# DolphinController.net
KiCad netlist of a schematic drawn in Altium Designer
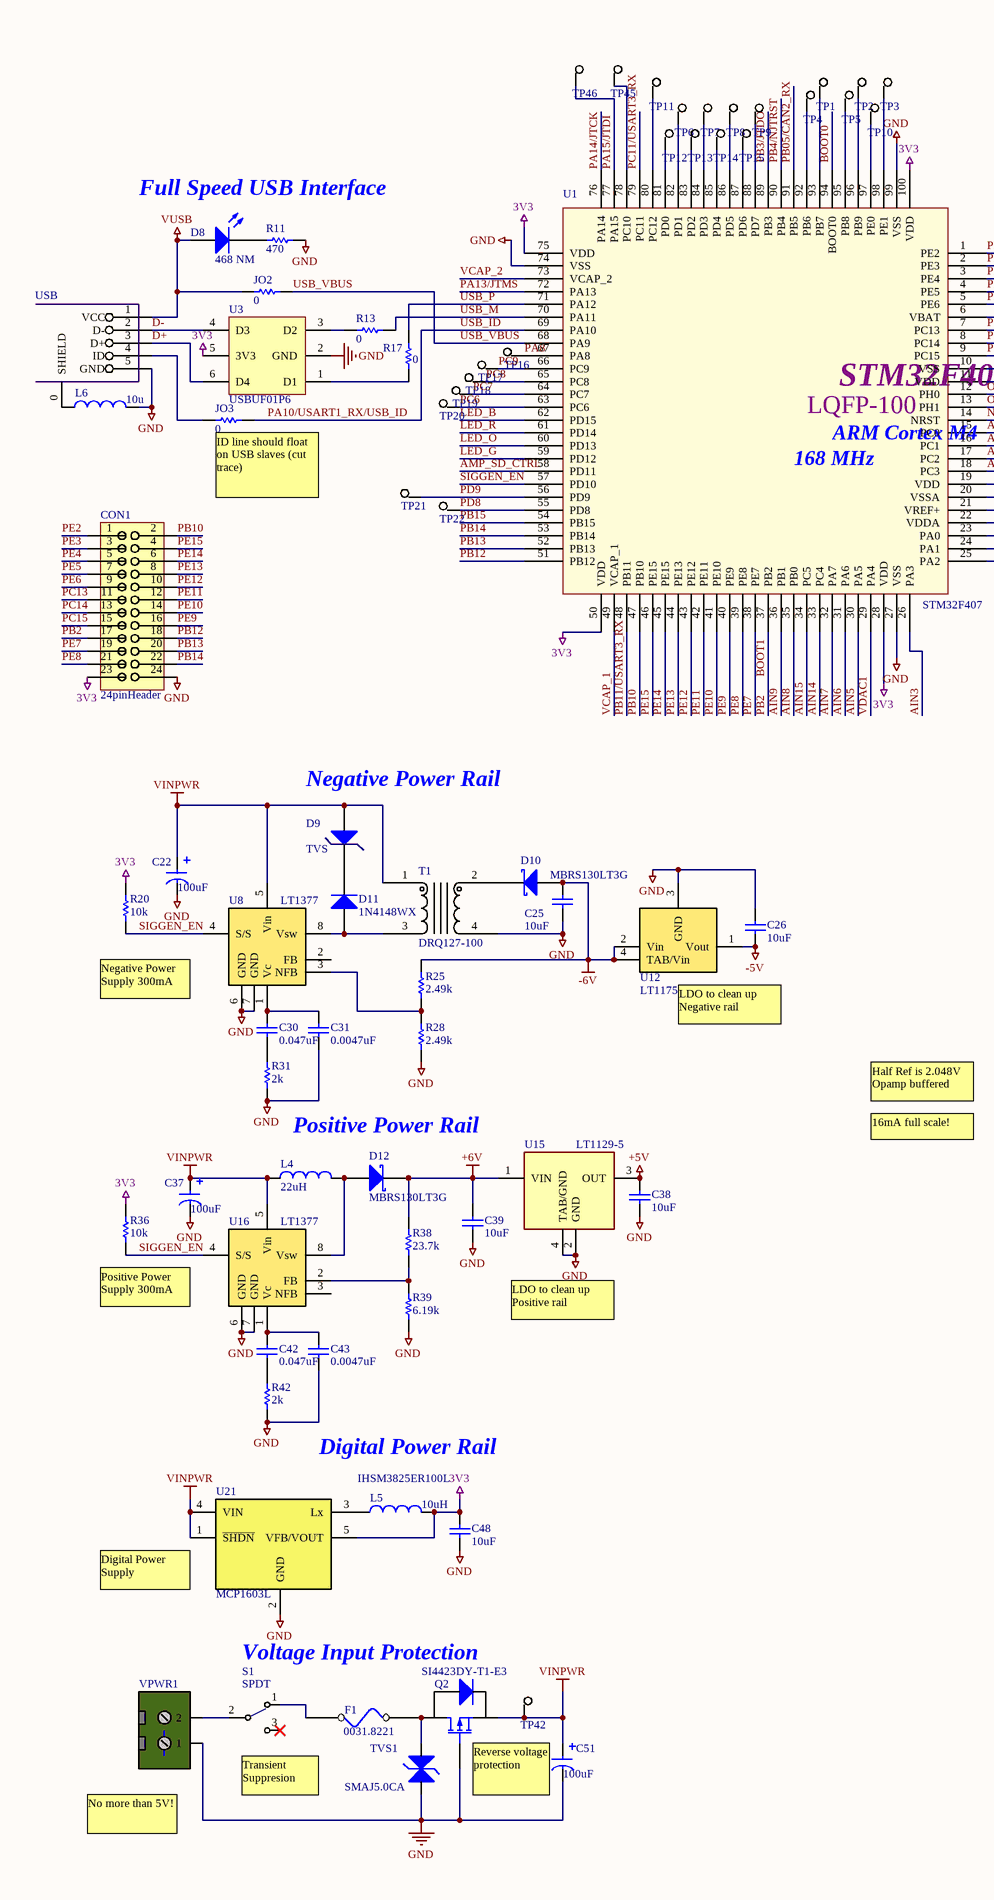
[diagram p0: DolphinController.SchDoc, left]
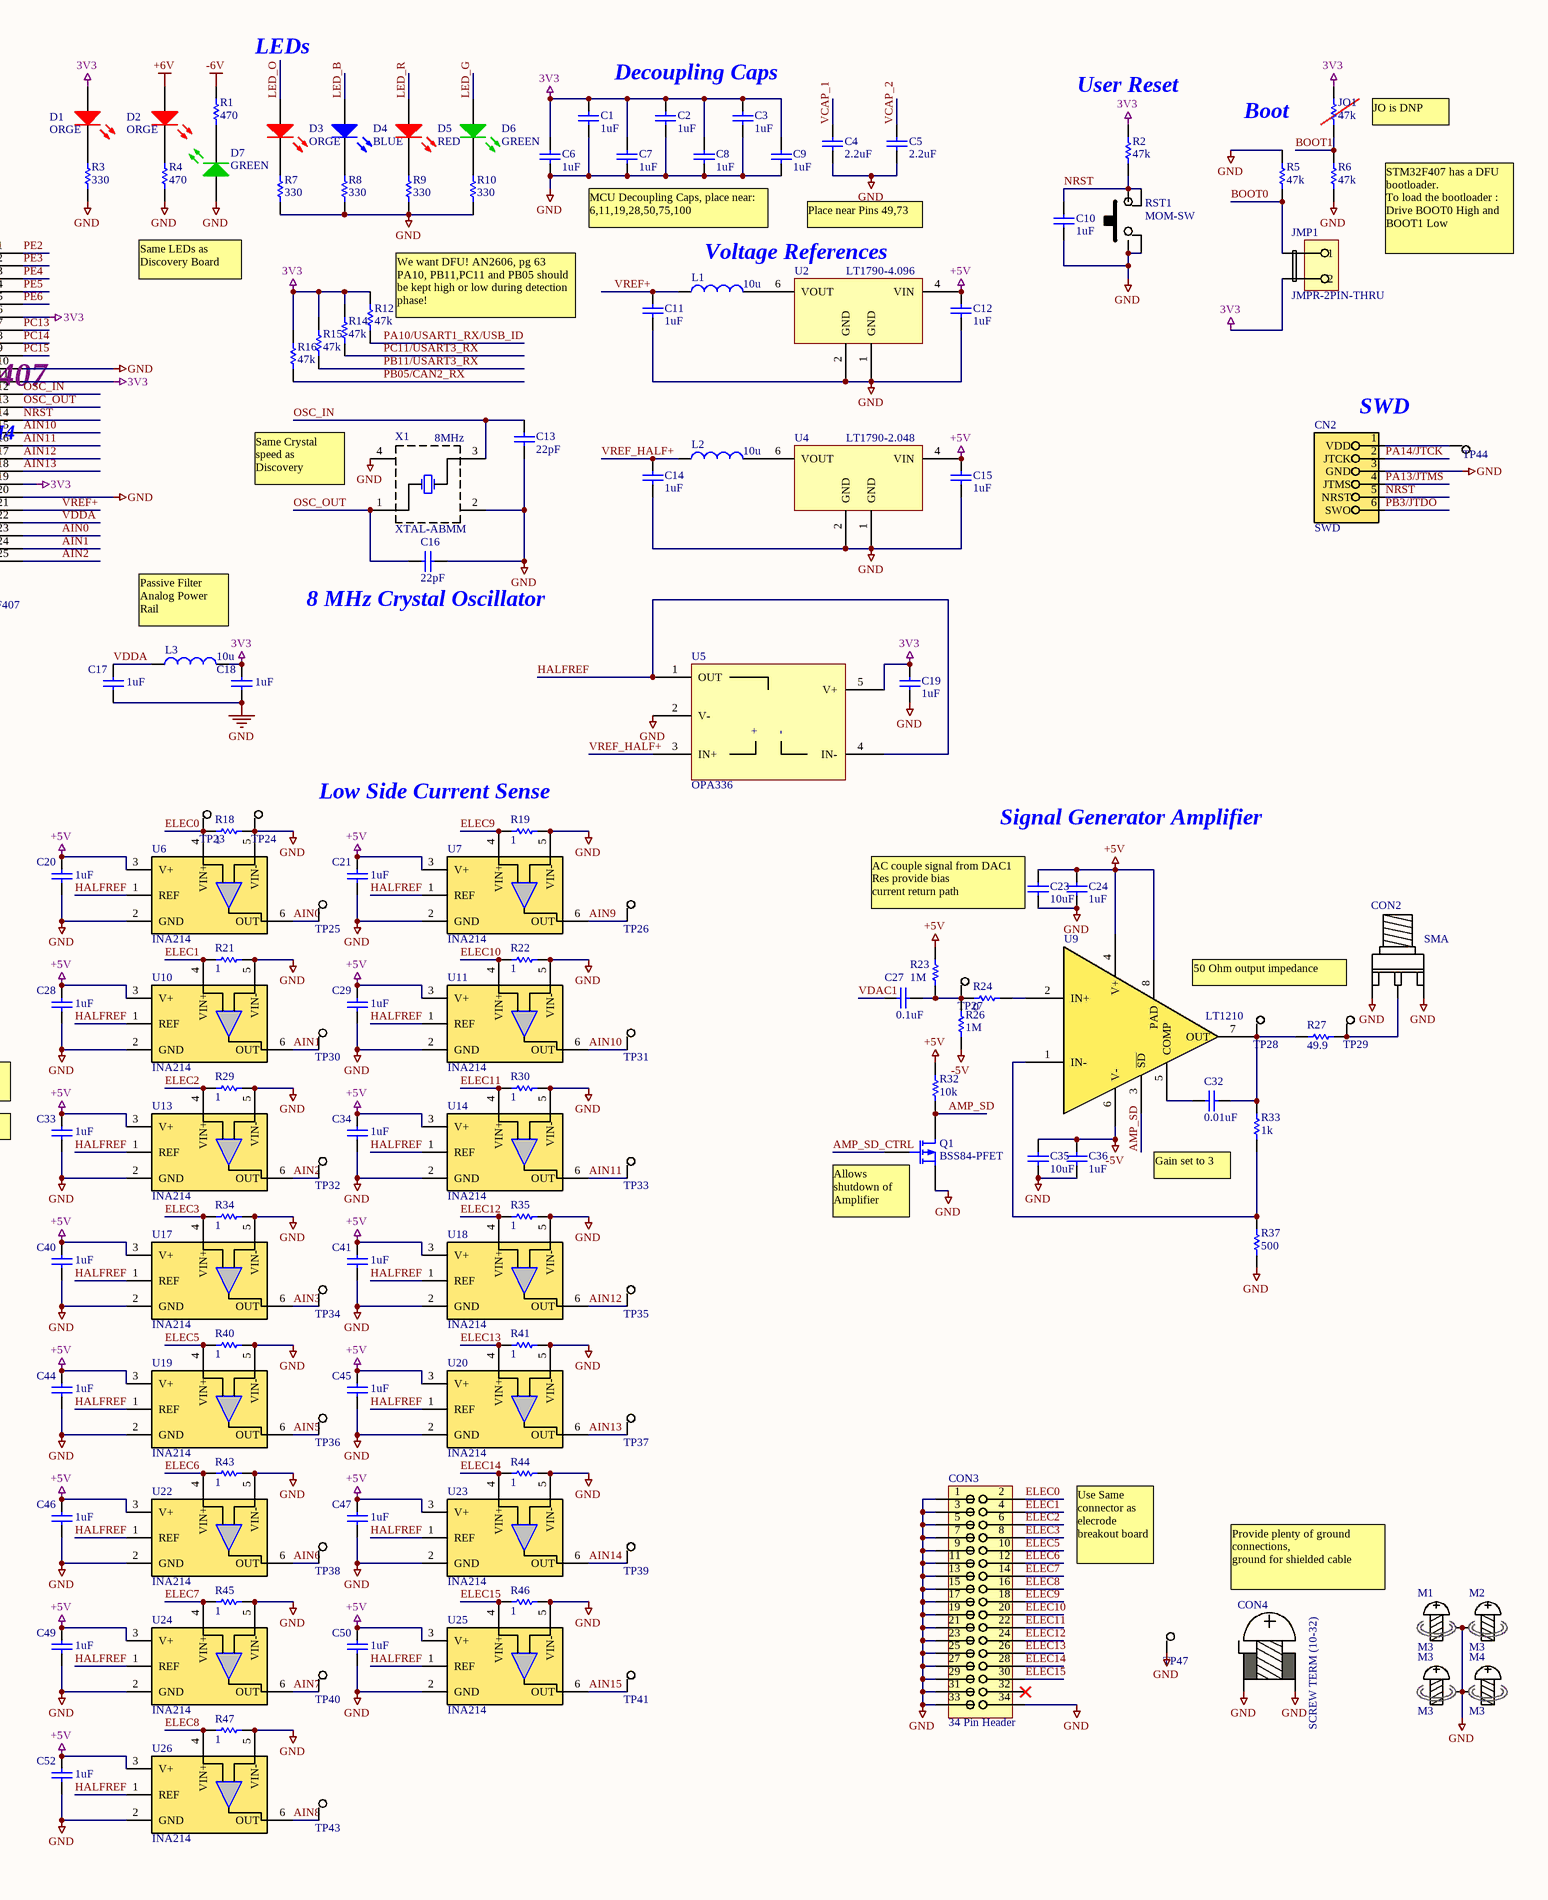
[diagram p1: DolphinController.SchDoc, right]

(export (version "E")
  (design (tool "Eeschema 10.0.6"))
  (components
    (comp (ref "C1")
      (value "CAP")
      (footprint "SM/C_0402")
      (fields (field (name "LABEL") "1uF"))
      (libsource (lib "Henry1_20_2010") (part "CAP"))
    )
    (comp (ref "C2")
      (value "CAP")
      (footprint "SM/C_0402")
      (fields (field (name "LABEL") "1uF"))
      (libsource (lib "Henry1_20_2010") (part "CAP"))
    )
    (comp (ref "C3")
      (value "CAP")
      (footprint "SM/C_0402")
      (fields (field (name "LABEL") "1uF"))
      (libsource (lib "Henry1_20_2010") (part "CAP"))
    )
    (comp (ref "C4")
      (value "CAP")
      (footprint "SM/C_0402")
      (fields (field (name "LABEL") "2.2uF"))
      (libsource (lib "Henry1_20_2010") (part "CAP"))
    )
    (comp (ref "C5")
      (value "CAP")
      (footprint "SM/C_0402")
      (fields (field (name "LABEL") "2.2uF"))
      (libsource (lib "Henry1_20_2010") (part "CAP"))
    )
    (comp (ref "C6")
      (value "CAP")
      (footprint "SM/C_0402")
      (fields (field (name "LABEL") "1uF"))
      (libsource (lib "Henry1_20_2010") (part "CAP"))
    )
    (comp (ref "C7")
      (value "CAP")
      (footprint "SM/C_0402")
      (fields (field (name "LABEL") "1uF"))
      (libsource (lib "Henry1_20_2010") (part "CAP"))
    )
    (comp (ref "C8")
      (value "CAP")
      (footprint "SM/C_0402")
      (fields (field (name "LABEL") "1uF"))
      (libsource (lib "Henry1_20_2010") (part "CAP"))
    )
    (comp (ref "C9")
      (value "CAP")
      (footprint "SM/C_0402")
      (fields (field (name "LABEL") "1uF"))
      (libsource (lib "Henry1_20_2010") (part "CAP"))
    )
    (comp (ref "C10")
      (value "CAP")
      (footprint "SM/C_0402")
      (fields (field (name "LABEL") "1uF"))
      (libsource (lib "Henry1_20_2010") (part "CAP"))
    )
    (comp (ref "C11")
      (value "CAP")
      (footprint "SM/C_0402")
      (fields (field (name "LABEL") "1uF"))
      (libsource (lib "Henry1_20_2010") (part "CAP"))
    )
    (comp (ref "C12")
      (value "CAP")
      (footprint "SM/C_0402")
      (fields (field (name "LABEL") "1uF"))
      (libsource (lib "Henry1_20_2010") (part "CAP"))
    )
    (comp (ref "C13")
      (value "CAP")
      (footprint "SM/C_0402")
      (fields (field (name "LABEL") "22pF"))
      (libsource (lib "Henry1_20_2010") (part "CAP"))
    )
    (comp (ref "C14")
      (value "CAP")
      (footprint "SM/C_0402")
      (fields (field (name "LABEL") "1uF"))
      (libsource (lib "Henry1_20_2010") (part "CAP"))
    )
    (comp (ref "C15")
      (value "CAP")
      (footprint "SM/C_0402")
      (fields (field (name "LABEL") "1uF"))
      (libsource (lib "Henry1_20_2010") (part "CAP"))
    )
    (comp (ref "C16")
      (value "CAP")
      (footprint "SM/C_0402")
      (fields (field (name "LABEL") "22pF"))
      (libsource (lib "Henry1_20_2010") (part "CAP"))
    )
    (comp (ref "C17")
      (value "CAP")
      (footprint "Henry:SM/C_0402")
      (fields (field (name "LABEL") "1uF"))
      (libsource (lib "Henry1_20_2010") (part "CAP"))
    )
    (comp (ref "C18")
      (value "CAP")
      (footprint "Henry:SM/C_0402")
      (fields (field (name "LABEL") "1uF"))
      (libsource (lib "Henry1_20_2010") (part "CAP"))
    )
    (comp (ref "C19")
      (value "CAP")
      (footprint "Henry:SM/C_0402")
      (fields (field (name "LABEL") "1uF"))
      (libsource (lib "Henry1_20_2010") (part "CAP"))
    )
    (comp (ref "C20")
      (value "CAP")
      (footprint "Henry:SM/C_0402")
      (fields (field (name "LABEL") "1uF"))
      (libsource (lib "Henry1_20_2010") (part "CAP"))
    )
    (comp (ref "C21")
      (value "CAP")
      (footprint "Henry:SM/C_0402")
      (fields (field (name "LABEL") "1uF"))
      (libsource (lib "Henry1_20_2010") (part "CAP"))
    )
    (comp (ref "C22")
      (value "CAP_POL")
      (footprint "SM/CT_6032_12")
      (description "CAP")
      (fields (field (name "LABEL") "100uF"))
      (libsource (lib "Henry1_20_2010") (part "CAP_POL"))
    )
    (comp (ref "C23")
      (value "CAP")
      (footprint "SM/C_0805")
      (fields (field (name "LABEL") "10uF"))
      (libsource (lib "Henry1_20_2010") (part "CAP"))
    )
    (comp (ref "C24")
      (value "CAP")
      (footprint "Henry:SM/C_0402")
      (fields (field (name "LABEL") "1uF"))
      (libsource (lib "Henry1_20_2010") (part "CAP"))
    )
    (comp (ref "C25")
      (value "CAP")
      (footprint "SM/C_0805")
      (fields (field (name "LABEL") "10uF"))
      (libsource (lib "Henry1_20_2010") (part "CAP"))
    )
    (comp (ref "C26")
      (value "CAP")
      (footprint "SM/C_0805")
      (fields (field (name "LABEL") "10uF"))
      (libsource (lib "Henry1_20_2010") (part "CAP"))
    )
    (comp (ref "C27")
      (value "CAP")
      (footprint "Henry:SM/C_0402")
      (fields (field (name "LABEL") "0.1uF"))
      (libsource (lib "Henry1_20_2010") (part "CAP"))
    )
    (comp (ref "C28")
      (value "CAP")
      (footprint "Henry:SM/C_0402")
      (fields (field (name "LABEL") "1uF"))
      (libsource (lib "Henry1_20_2010") (part "CAP"))
    )
    (comp (ref "C29")
      (value "CAP")
      (footprint "Henry:SM/C_0402")
      (fields (field (name "LABEL") "1uF"))
      (libsource (lib "Henry1_20_2010") (part "CAP"))
    )
    (comp (ref "C30")
      (value "CAP")
      (footprint "Henry:SM/C_0402")
      (fields (field (name "LABEL") "0.047uF"))
      (libsource (lib "Henry1_20_2010") (part "CAP"))
    )
    (comp (ref "C31")
      (value "CAP")
      (footprint "Henry:SM/C_0402")
      (fields (field (name "LABEL") "0.0047uF"))
      (libsource (lib "Henry1_20_2010") (part "CAP"))
    )
    (comp (ref "C32")
      (value "CAP")
      (footprint "Henry:SM/C_0402")
      (fields (field (name "LABEL") "0.01uF"))
      (libsource (lib "Henry1_20_2010") (part "CAP"))
    )
    (comp (ref "C33")
      (value "CAP")
      (footprint "Henry:SM/C_0402")
      (fields (field (name "LABEL") "1uF"))
      (libsource (lib "Henry1_20_2010") (part "CAP"))
    )
    (comp (ref "C34")
      (value "CAP")
      (footprint "Henry:SM/C_0402")
      (fields (field (name "LABEL") "1uF"))
      (libsource (lib "Henry1_20_2010") (part "CAP"))
    )
    (comp (ref "C35")
      (value "CAP")
      (footprint "SM/C_0805")
      (fields (field (name "LABEL") "10uF"))
      (libsource (lib "Henry1_20_2010") (part "CAP"))
    )
    (comp (ref "C36")
      (value "CAP")
      (footprint "Henry:SM/C_0402")
      (fields (field (name "LABEL") "1uF"))
      (libsource (lib "Henry1_20_2010") (part "CAP"))
    )
    (comp (ref "C37")
      (value "CAP_POL")
      (footprint "SM/CT_6032_12")
      (description "CAP")
      (fields (field (name "LABEL") "100uF"))
      (libsource (lib "Henry1_20_2010") (part "CAP_POL"))
    )
    (comp (ref "C38")
      (value "CAP")
      (footprint "SM/C_0805")
      (fields (field (name "LABEL") "10uF"))
      (libsource (lib "Henry1_20_2010") (part "CAP"))
    )
    (comp (ref "C39")
      (value "CAP")
      (footprint "SM/C_0805")
      (fields (field (name "LABEL") "10uF"))
      (libsource (lib "Henry1_20_2010") (part "CAP"))
    )
    (comp (ref "C40")
      (value "CAP")
      (footprint "Henry:SM/C_0402")
      (fields (field (name "LABEL") "1uF"))
      (libsource (lib "Henry1_20_2010") (part "CAP"))
    )
    (comp (ref "C41")
      (value "CAP")
      (footprint "Henry:SM/C_0402")
      (fields (field (name "LABEL") "1uF"))
      (libsource (lib "Henry1_20_2010") (part "CAP"))
    )
    (comp (ref "C42")
      (value "CAP")
      (footprint "Henry:SM/C_0402")
      (fields (field (name "LABEL") "0.047uF"))
      (libsource (lib "Henry1_20_2010") (part "CAP"))
    )
    (comp (ref "C43")
      (value "CAP")
      (footprint "Henry:SM/C_0402")
      (fields (field (name "LABEL") "0.0047uF"))
      (libsource (lib "Henry1_20_2010") (part "CAP"))
    )
    (comp (ref "C44")
      (value "CAP")
      (footprint "Henry:SM/C_0402")
      (fields (field (name "LABEL") "1uF"))
      (libsource (lib "Henry1_20_2010") (part "CAP"))
    )
    (comp (ref "C45")
      (value "CAP")
      (footprint "Henry:SM/C_0402")
      (fields (field (name "LABEL") "1uF"))
      (libsource (lib "Henry1_20_2010") (part "CAP"))
    )
    (comp (ref "C46")
      (value "CAP")
      (footprint "Henry:SM/C_0402")
      (fields (field (name "LABEL") "1uF"))
      (libsource (lib "Henry1_20_2010") (part "CAP"))
    )
    (comp (ref "C47")
      (value "CAP")
      (footprint "Henry:SM/C_0402")
      (fields (field (name "LABEL") "1uF"))
      (libsource (lib "Henry1_20_2010") (part "CAP"))
    )
    (comp (ref "C48")
      (value "CAP")
      (footprint "SM/C_0805")
      (fields (field (name "LABEL") "10uF"))
      (libsource (lib "Henry1_20_2010") (part "CAP"))
    )
    (comp (ref "C49")
      (value "CAP")
      (footprint "Henry:SM/C_0402")
      (fields (field (name "LABEL") "1uF"))
      (libsource (lib "Henry1_20_2010") (part "CAP"))
    )
    (comp (ref "C50")
      (value "CAP")
      (footprint "Henry:SM/C_0402")
      (fields (field (name "LABEL") "1uF"))
      (libsource (lib "Henry1_20_2010") (part "CAP"))
    )
    (comp (ref "C51")
      (value "CAP_POL")
      (footprint "SM/CT_6032_12")
      (description "CAP")
      (fields (field (name "LABEL") "100uF"))
      (libsource (lib "Henry1_20_2010") (part "CAP_POL"))
    )
    (comp (ref "C52")
      (value "CAP")
      (footprint "Henry:SM/C_0402")
      (fields (field (name "LABEL") "1uF"))
      (libsource (lib "Henry1_20_2010") (part "CAP"))
    )
    (comp (ref "CN2") (value "SWD") (libsource (lib "Henry1_20_2010") (part "SWD-STM32F4-Program-Header")))
    (comp (ref "CON1")
      (value "24pinHeader")
      (footprint "CONN-RECEPT-24PIN")
      (libsource (lib "Henry1_20_2010") (part "24pinHeader"))
    )
    (comp (ref "CON2")
      (value "SMA")
      (footprint "SMA-SMA-VERT")
      (libsource (lib "Henry1_20_2010") (part "SMA-THRU-VERT"))
    )
    (comp (ref "CON3")
      (value "34 Pin Header")
      (footprint "34Pin-Rectangular Header-SurfaceMount-100milSpacing")
      (libsource (lib "Henry1_20_2010") (part "34pinHeader"))
    )
    (comp (ref "CON4")
      (value "SCREW TERM (10-32)")
      (footprint "LOW-PROFILE-SCREWTERMINAL")
      (libsource (lib "Henry1_20_2010") (part "ScrewTerminal-PCB-ThruHole"))
    )
    (comp (ref "D1")
      (value "ORGE")
      (footprint "LED-0603")
      (description "LED SUPER RED CLEAR 0603 SMD")
      (fields (field (name "MFRPARTNUM") "LTST-C190KRKT") (field (name "PUBLISHER") "Altium Limited"))
      (libsource (lib "FriedParts") (part "LITEON/LED RED"))
    )
    (comp (ref "D2")
      (value "ORGE")
      (footprint "LED-0603")
      (description "LED SUPER RED CLEAR 0603 SMD")
      (fields (field (name "MFRPARTNUM") "LTST-C190KRKT") (field (name "PUBLISHER") "Altium Limited"))
      (libsource (lib "FriedParts") (part "LITEON/LED RED"))
    )
    (comp (ref "D3")
      (value "ORGE")
      (footprint "LED-0603")
      (description "LED SUPER RED CLEAR 0603 SMD")
      (fields (field (name "MFRPARTNUM") "LTST-C190KRKT") (field (name "PUBLISHER") "Altium Limited"))
      (libsource (lib "FriedParts") (part "LITEON/LED RED"))
    )
    (comp (ref "D4")
      (value "BLUE")
      (footprint "LED-0603")
      (description "LED 468NM BLUE CLEAR 0603 SMD")
      (fields (field (name "MFRPARTNUM") "LTST-C190TBKT") (field (name "PUBLISHER") "Altium Limited"))
      (libsource (lib "FriedParts") (part "LITEON/LED BLUE"))
    )
    (comp (ref "D5")
      (value "RED")
      (footprint "LED-0603")
      (description "LED SUPER RED CLEAR 0603 SMD")
      (fields (field (name "MFRPARTNUM") "LTST-C190KRKT") (field (name "PUBLISHER") "Altium Limited"))
      (libsource (lib "FriedParts") (part "LITEON/LED RED"))
    )
    (comp (ref "D6")
      (value "GREEN")
      (footprint "LED-0603")
      (description "LED GREEN CLEAR 0603 SMD")
      (fields (field (name "MFRPARTNUM") "LTST-C190GKT") (field (name "PUBLISHER") "Altium Limited"))
      (libsource (lib "FriedParts") (part "LITEON/LED GREEN"))
    )
    (comp (ref "D7")
      (value "GREEN")
      (footprint "LED-0603")
      (description "LED GREEN CLEAR 0603 SMD")
      (fields (field (name "MFRPARTNUM") "LTST-C190GKT") (field (name "PUBLISHER") "Altium Limited"))
      (libsource (lib "FriedParts") (part "LITEON/LED GREEN"))
    )
    (comp (ref "D8")
      (value "468 NM")
      (footprint "LED-0603")
      (description "LED 468NM BLUE CLEAR 0603 SMD")
      (fields (field (name "MFRPARTNUM") "LTST-C190TBKT") (field (name "PUBLISHER") "Altium Limited"))
      (libsource (lib "FriedParts") (part "LITEON/LED BLUE"))
    )
    (comp (ref "D9") (value "TVS") (footprint "D0-214AC") (libsource (lib "Henry1_20_2010") (part "TVS")))
    (comp (ref "D10")
      (value "MBRS130LT3G")
      (footprint "D0-214AC")
      (libsource (lib "Henry1_20_2010") (part "Schottky Diode_AC"))
    )
    (comp (ref "D11")
      (value "1N4148WX")
      (footprint "SOD323 - MCC - 1N4148WX")
      (libsource (lib "Henry1_20_2010") (part "Diode-1N4148WX"))
    )
    (comp (ref "D12")
      (value "MBRS130LT3G")
      (footprint "D0-214AC")
      (libsource (lib "Henry1_20_2010") (part "Schottky Diode_AC"))
    )
    (comp (ref "F1")
      (value "0031.8221")
      (footprint "SCHURTER/SMD/2 PADS/0031.8221")
      (description "FUSEHOLDER BLACK FOR SMD 5X20MM")
      (libsource (lib "FriedParts") (part "FUSE"))
    )
    (comp (ref "JMP1")
      (value "JMPR-2PIN-THRU")
      (footprint "M02")
      (libsource (lib "Henry1_20_2010") (part "JMPR-2PIN-THRU"))
    )
    (comp (ref "JO1")
      (value "47k")
      (footprint "SM/R_0402")
      (description "Resistor")
      (fields (field (name "Comment") "Res") (field (name "PUBLISHER") "Altium Limited"))
      (libsource (lib "Henry1_20_2010") (part "Res"))
    )
    (comp (ref "JO2")
      (value "0")
      (footprint "SM/R_0402")
      (description "Resistor")
      (fields (field (name "Comment") "Res") (field (name "PUBLISHER") "Altium Limited"))
      (libsource (lib "Henry1_20_2010") (part "Res"))
    )
    (comp (ref "JO3")
      (value "0")
      (footprint "SM/R_0402")
      (description "Resistor")
      (fields (field (name "Comment") "Res") (field (name "PUBLISHER") "Altium Limited"))
      (libsource (lib "Henry1_20_2010") (part "Res"))
    )
    (comp (ref "L1")
      (value "10u")
      (footprint "SM/L_0805")
      (fields (field (name "Comment") "Inductor"))
      (libsource (lib "Henry1_20_2010") (part "Inductor"))
    )
    (comp (ref "L2")
      (value "10u")
      (footprint "SM/L_0805")
      (fields (field (name "Comment") "Inductor"))
      (libsource (lib "Henry1_20_2010") (part "Inductor"))
    )
    (comp (ref "L3")
      (value "10u")
      (footprint "SM/L_0805")
      (fields (field (name "Comment") "Inductor"))
      (libsource (lib "Henry1_20_2010") (part "Inductor"))
    )
    (comp (ref "L4")
      (value "22uH")
      (footprint "G_JMETRIC/TDK/SLE10145")
      (description "INDUCTOR SHIELD PWR 22UH 10145")
      (fields (field (name "MFRPARTNUM") "SLF10145T-220M1R9-PF"))
      (libsource (lib "FriedParts") (part "INDUCTOR"))
    )
    (comp (ref "L5")
      (value "IHSM3825ER100L")
      (footprint "INDUCTOR POWER 10UH 1.74A SMD")
      (fields (field (name "ALTIUM_VALUE") "10uH"))
      (libsource (lib "Henry1_20_2010") (part "INDUCTOR_POWER_10UH_1.74A_SMD"))
    )
    (comp (ref "L6")
      (value "10u")
      (footprint "SM/L_0805")
      (fields (field (name "Comment") "Inductor"))
      (libsource (lib "Henry1_20_2010") (part "Inductor"))
    )
    (comp (ref "M1")
      (value "M3")
      (footprint "MOUNTING_HOLE-125mil")
      (libsource (lib "") (part "MountingHole_1"))
    )
    (comp (ref "M2")
      (value "M3")
      (footprint "MOUNTING_HOLE-125mil")
      (libsource (lib "Henry1_20_2010") (part "MountingHole"))
    )
    (comp (ref "M3")
      (value "M3")
      (footprint "MOUNTING_HOLE-125mil")
      (libsource (lib "") (part "MountingHole_1"))
    )
    (comp (ref "M4")
      (value "M3")
      (footprint "MOUNTING_HOLE-125mil")
      (libsource (lib "Henry1_20_2010") (part "MountingHole"))
    )
    (comp (ref "Q1")
      (value "BSS84-PFET")
      (footprint "SOT23-BSS84-P-MOSFET")
      (description "P-Channel MOSFET")
      (fields (field (name "PUBLISHER") "Altium Limited"))
      (libsource (lib "Henry1_20_2010") (part "BSS84-MOSFET-P"))
    )
    (comp (ref "Q2")
      (value "SI4423DY-T1-E3")
      (footprint "SOIC-8-Lead-Vishay-PFET")
      (description "mosfet,p ch,20v,10a,8soic; transistor polarity:p channel;")
      (libsource (lib "FriedParts") (part "P-Channel 20V D-S MOSFET"))
    )
    (comp (ref "R1")
      (value "470")
      (footprint "SM/R_0402")
      (description "Resistor")
      (fields (field (name "Comment") "Res") (field (name "PUBLISHER") "Altium Limited"))
      (libsource (lib "Henry1_20_2010") (part "Res"))
    )
    (comp (ref "R2")
      (value "47k")
      (footprint "Henry:SM/R_0402")
      (description "Resistor")
      (fields (field (name "Comment") "Res") (field (name "PUBLISHER") "Altium Limited"))
      (libsource (lib "Henry1_20_2010") (part "Res"))
    )
    (comp (ref "R3")
      (value "330")
      (footprint "SM/R_0402")
      (description "Resistor")
      (fields (field (name "Comment") "Res") (field (name "PUBLISHER") "Altium Limited"))
      (libsource (lib "Henry1_20_2010") (part "Res"))
    )
    (comp (ref "R4")
      (value "470")
      (footprint "SM/R_0402")
      (description "Resistor")
      (fields (field (name "Comment") "Res") (field (name "PUBLISHER") "Altium Limited"))
      (libsource (lib "Henry1_20_2010") (part "Res"))
    )
    (comp (ref "R5")
      (value "47k")
      (footprint "SM/R_0402")
      (description "Resistor")
      (fields (field (name "Comment") "Res") (field (name "PUBLISHER") "Altium Limited"))
      (libsource (lib "Henry1_20_2010") (part "Res"))
    )
    (comp (ref "R6")
      (value "47k")
      (footprint "SM/R_0402")
      (description "Resistor")
      (fields (field (name "Comment") "Res") (field (name "PUBLISHER") "Altium Limited"))
      (libsource (lib "Henry1_20_2010") (part "Res"))
    )
    (comp (ref "R7")
      (value "330")
      (footprint "SM/R_0402")
      (description "Resistor")
      (fields (field (name "Comment") "Res") (field (name "PUBLISHER") "Altium Limited"))
      (libsource (lib "Henry1_20_2010") (part "Res"))
    )
    (comp (ref "R8")
      (value "330")
      (footprint "SM/R_0402")
      (description "Resistor")
      (fields (field (name "Comment") "Res") (field (name "PUBLISHER") "Altium Limited"))
      (libsource (lib "Henry1_20_2010") (part "Res"))
    )
    (comp (ref "R9")
      (value "330")
      (footprint "SM/R_0402")
      (description "Resistor")
      (fields (field (name "Comment") "Res") (field (name "PUBLISHER") "Altium Limited"))
      (libsource (lib "Henry1_20_2010") (part "Res"))
    )
    (comp (ref "R10")
      (value "330")
      (footprint "SM/R_0402")
      (description "Resistor")
      (fields (field (name "Comment") "Res") (field (name "PUBLISHER") "Altium Limited"))
      (libsource (lib "Henry1_20_2010") (part "Res"))
    )
    (comp (ref "R11")
      (value "470")
      (footprint "SM/R_0402")
      (description "Resistor")
      (fields (field (name "Comment") "Res") (field (name "PUBLISHER") "Altium Limited"))
      (libsource (lib "Henry1_20_2010") (part "Res"))
    )
    (comp (ref "R12")
      (value "47k")
      (footprint "SM/R_0402")
      (description "Resistor")
      (fields (field (name "Comment") "Res") (field (name "PUBLISHER") "Altium Limited"))
      (libsource (lib "Henry1_20_2010") (part "Res"))
    )
    (comp (ref "R13")
      (value "0")
      (footprint "SM/R_0402")
      (description "Resistor")
      (fields (field (name "Comment") "Res") (field (name "PUBLISHER") "Altium Limited"))
      (libsource (lib "Henry1_20_2010") (part "Res"))
    )
    (comp (ref "R14")
      (value "47k")
      (footprint "SM/R_0402")
      (description "Resistor")
      (fields (field (name "Comment") "Res") (field (name "PUBLISHER") "Altium Limited"))
      (libsource (lib "Henry1_20_2010") (part "Res"))
    )
    (comp (ref "R15")
      (value "47k")
      (footprint "SM/R_0402")
      (description "Resistor")
      (fields (field (name "Comment") "Res") (field (name "PUBLISHER") "Altium Limited"))
      (libsource (lib "Henry1_20_2010") (part "Res"))
    )
    (comp (ref "R16")
      (value "47k")
      (footprint "SM/R_0402")
      (description "Resistor")
      (fields (field (name "Comment") "Res") (field (name "PUBLISHER") "Altium Limited"))
      (libsource (lib "Henry1_20_2010") (part "Res"))
    )
    (comp (ref "R17")
      (value "0")
      (footprint "SM/R_0402")
      (description "Resistor")
      (fields (field (name "Comment") "Res") (field (name "PUBLISHER") "Altium Limited"))
      (libsource (lib "Henry1_20_2010") (part "Res"))
    )
    (comp (ref "R18")
      (value "1")
      (footprint "SM/R_1206")
      (description "Resistor")
      (fields (field (name "Comment") "Res") (field (name "PUBLISHER") "Altium Limited"))
      (libsource (lib "Henry1_20_2010") (part "Res"))
    )
    (comp (ref "R19")
      (value "1")
      (footprint "SM/R_1206")
      (description "Resistor")
      (fields (field (name "Comment") "Res") (field (name "PUBLISHER") "Altium Limited"))
      (libsource (lib "Henry1_20_2010") (part "Res"))
    )
    (comp (ref "R20")
      (value "10k")
      (footprint "SM/R_0402")
      (description "Resistor")
      (fields (field (name "Comment") "Res") (field (name "PUBLISHER") "Altium Limited"))
      (libsource (lib "Henry1_20_2010") (part "Res"))
    )
    (comp (ref "R21")
      (value "1")
      (footprint "SM/R_1206")
      (description "Resistor")
      (fields (field (name "Comment") "Res") (field (name "PUBLISHER") "Altium Limited"))
      (libsource (lib "Henry1_20_2010") (part "Res"))
    )
    (comp (ref "R22")
      (value "1")
      (footprint "SM/R_1206")
      (description "Resistor")
      (fields (field (name "Comment") "Res") (field (name "PUBLISHER") "Altium Limited"))
      (libsource (lib "Henry1_20_2010") (part "Res"))
    )
    (comp (ref "R23")
      (value "1M")
      (footprint "SM/R_0402")
      (description "Resistor")
      (fields (field (name "Comment") "Res") (field (name "PUBLISHER") "Altium Limited"))
      (libsource (lib "Henry1_20_2010") (part "Res"))
    )
    (comp (ref "R24")
      (value "0")
      (footprint "SM/R_0402")
      (description "Resistor")
      (fields (field (name "Comment") "Res") (field (name "PUBLISHER") "Altium Limited"))
      (libsource (lib "Henry1_20_2010") (part "Res"))
    )
    (comp (ref "R25")
      (value "2.49k")
      (footprint "SM/R_0402")
      (description "Resistor")
      (fields (field (name "Comment") "Res") (field (name "PUBLISHER") "Altium Limited"))
      (libsource (lib "Henry1_20_2010") (part "Res"))
    )
    (comp (ref "R26")
      (value "1M")
      (footprint "SM/R_0402")
      (description "Resistor")
      (fields (field (name "Comment") "Res") (field (name "PUBLISHER") "Altium Limited"))
      (libsource (lib "Henry1_20_2010") (part "Res"))
    )
    (comp (ref "R27")
      (value "49.9")
      (footprint "SM/R_2512")
      (description "Resistor")
      (fields (field (name "Comment") "Res") (field (name "PUBLISHER") "Altium Limited"))
      (libsource (lib "Henry1_20_2010") (part "Res"))
    )
    (comp (ref "R28")
      (value "2.49k")
      (footprint "SM/R_0402")
      (description "Resistor")
      (fields (field (name "Comment") "Res") (field (name "PUBLISHER") "Altium Limited"))
      (libsource (lib "Henry1_20_2010") (part "Res"))
    )
    (comp (ref "R29")
      (value "1")
      (footprint "SM/R_1206")
      (description "Resistor")
      (fields (field (name "Comment") "Res") (field (name "PUBLISHER") "Altium Limited"))
      (libsource (lib "Henry1_20_2010") (part "Res"))
    )
    (comp (ref "R30")
      (value "1")
      (footprint "SM/R_1206")
      (description "Resistor")
      (fields (field (name "Comment") "Res") (field (name "PUBLISHER") "Altium Limited"))
      (libsource (lib "Henry1_20_2010") (part "Res"))
    )
    (comp (ref "R31")
      (value "2k")
      (footprint "SM/R_0402")
      (description "Resistor")
      (fields (field (name "Comment") "Res") (field (name "PUBLISHER") "Altium Limited"))
      (libsource (lib "Henry1_20_2010") (part "Res"))
    )
    (comp (ref "R32")
      (value "10k")
      (footprint "SM/R_0402")
      (description "Resistor")
      (fields (field (name "Comment") "Res") (field (name "PUBLISHER") "Altium Limited"))
      (libsource (lib "Henry1_20_2010") (part "Res"))
    )
    (comp (ref "R33")
      (value "1k")
      (footprint "SM/R_0402")
      (description "Resistor")
      (fields (field (name "Comment") "Res") (field (name "PUBLISHER") "Altium Limited"))
      (libsource (lib "Henry1_20_2010") (part "Res"))
    )
    (comp (ref "R34")
      (value "1")
      (footprint "SM/R_1206")
      (description "Resistor")
      (fields (field (name "Comment") "Res") (field (name "PUBLISHER") "Altium Limited"))
      (libsource (lib "Henry1_20_2010") (part "Res"))
    )
    (comp (ref "R35")
      (value "1")
      (footprint "SM/R_1206")
      (description "Resistor")
      (fields (field (name "Comment") "Res") (field (name "PUBLISHER") "Altium Limited"))
      (libsource (lib "Henry1_20_2010") (part "Res"))
    )
    (comp (ref "R36")
      (value "10k")
      (footprint "SM/R_0402")
      (description "Resistor")
      (fields (field (name "Comment") "Res") (field (name "PUBLISHER") "Altium Limited"))
      (libsource (lib "Henry1_20_2010") (part "Res"))
    )
    (comp (ref "R37")
      (value "500")
      (footprint "SM/R_0402")
      (description "Resistor")
      (fields (field (name "Comment") "Res") (field (name "PUBLISHER") "Altium Limited"))
      (libsource (lib "Henry1_20_2010") (part "Res"))
    )
    (comp (ref "R38")
      (value "23.7k")
      (footprint "SM/R_0402")
      (description "Resistor")
      (fields (field (name "Comment") "Res") (field (name "PUBLISHER") "Altium Limited"))
      (libsource (lib "Henry1_20_2010") (part "Res"))
    )
    (comp (ref "R39")
      (value "6.19k")
      (footprint "SM/R_0402")
      (description "Resistor")
      (fields (field (name "Comment") "Res") (field (name "PUBLISHER") "Altium Limited"))
      (libsource (lib "Henry1_20_2010") (part "Res"))
    )
    (comp (ref "R40")
      (value "1")
      (footprint "SM/R_1206")
      (description "Resistor")
      (fields (field (name "Comment") "Res") (field (name "PUBLISHER") "Altium Limited"))
      (libsource (lib "Henry1_20_2010") (part "Res"))
    )
    (comp (ref "R41")
      (value "1")
      (footprint "SM/R_1206")
      (description "Resistor")
      (fields (field (name "Comment") "Res") (field (name "PUBLISHER") "Altium Limited"))
      (libsource (lib "Henry1_20_2010") (part "Res"))
    )
    (comp (ref "R42")
      (value "2k")
      (footprint "SM/R_0402")
      (description "Resistor")
      (fields (field (name "Comment") "Res") (field (name "PUBLISHER") "Altium Limited"))
      (libsource (lib "Henry1_20_2010") (part "Res"))
    )
    (comp (ref "R43")
      (value "1")
      (footprint "SM/R_1206")
      (description "Resistor")
      (fields (field (name "Comment") "Res") (field (name "PUBLISHER") "Altium Limited"))
      (libsource (lib "Henry1_20_2010") (part "Res"))
    )
    (comp (ref "R44")
      (value "1")
      (footprint "SM/R_1206")
      (description "Resistor")
      (fields (field (name "Comment") "Res") (field (name "PUBLISHER") "Altium Limited"))
      (libsource (lib "Henry1_20_2010") (part "Res"))
    )
    (comp (ref "R45")
      (value "1")
      (footprint "SM/R_1206")
      (description "Resistor")
      (fields (field (name "Comment") "Res") (field (name "PUBLISHER") "Altium Limited"))
      (libsource (lib "Henry1_20_2010") (part "Res"))
    )
    (comp (ref "R46")
      (value "1")
      (footprint "SM/R_1206")
      (description "Resistor")
      (fields (field (name "Comment") "Res") (field (name "PUBLISHER") "Altium Limited"))
      (libsource (lib "Henry1_20_2010") (part "Res"))
    )
    (comp (ref "R47")
      (value "1")
      (footprint "SM/R_1206")
      (description "Resistor")
      (fields (field (name "Comment") "Res") (field (name "PUBLISHER") "Altium Limited"))
      (libsource (lib "Henry1_20_2010") (part "Res"))
    )
    (comp (ref "RST1")
      (value "MOM-SW")
      (footprint "MOM-SW")
      (libsource (lib "Henry1_20_2010") (part "MOM-TACT-SW"))
    )
    (comp (ref "S1")
      (value "SPDT")
      (footprint "SW_Lseries")
      (description "SPDT slide right angle TH high current switch")
      (libsource (lib "PaulMartin") (part "SPDT-TH"))
    )
    (comp (ref "T1")
      (value "DRQ127-100")
      (footprint "DRQ127-100")
      (libsource (lib "Henry1_20_2010") (part "DRQ127-100-XFORM-1{colon}1"))
    )
    (comp (ref "TP1")
      (value "TEST_PT")
      (footprint "TEST_PT_SMD")
      (libsource (lib "Henry1_20_2010") (part "TEST_PT"))
    )
    (comp (ref "TP2")
      (value "TEST_PT")
      (footprint "TEST_PT_SMD")
      (libsource (lib "Henry1_20_2010") (part "TEST_PT"))
    )
    (comp (ref "TP3")
      (value "TEST_PT")
      (footprint "TEST_PT_SMD")
      (libsource (lib "Henry1_20_2010") (part "TEST_PT"))
    )
    (comp (ref "TP4")
      (value "TEST_PT")
      (footprint "TEST_PT_SMD")
      (libsource (lib "Henry1_20_2010") (part "TEST_PT"))
    )
    (comp (ref "TP5")
      (value "TEST_PT")
      (footprint "TEST_PT_SMD")
      (libsource (lib "Henry1_20_2010") (part "TEST_PT"))
    )
    (comp (ref "TP6")
      (value "TEST_PT")
      (footprint "TEST_PT_SMD")
      (libsource (lib "Henry1_20_2010") (part "TEST_PT"))
    )
    (comp (ref "TP7")
      (value "TEST_PT")
      (footprint "TEST_PT_SMD")
      (libsource (lib "Henry1_20_2010") (part "TEST_PT"))
    )
    (comp (ref "TP8")
      (value "TEST_PT")
      (footprint "TEST_PT_SMD")
      (libsource (lib "Henry1_20_2010") (part "TEST_PT"))
    )
    (comp (ref "TP9")
      (value "TEST_PT")
      (footprint "TEST_PT_SMD")
      (libsource (lib "Henry1_20_2010") (part "TEST_PT"))
    )
    (comp (ref "TP10")
      (value "TEST_PT")
      (footprint "TEST_PT_SMD")
      (libsource (lib "Henry1_20_2010") (part "TEST_PT"))
    )
    (comp (ref "TP11")
      (value "TEST_PT")
      (footprint "TEST_PT_SMD")
      (libsource (lib "Henry1_20_2010") (part "TEST_PT"))
    )
    (comp (ref "TP12")
      (value "TEST_PT")
      (footprint "TEST_PT_SMD")
      (libsource (lib "Henry1_20_2010") (part "TEST_PT"))
    )
    (comp (ref "TP13")
      (value "TEST_PT")
      (footprint "TEST_PT_SMD")
      (libsource (lib "Henry1_20_2010") (part "TEST_PT"))
    )
    (comp (ref "TP14")
      (value "TEST_PT")
      (footprint "TEST_PT_SMD")
      (libsource (lib "Henry1_20_2010") (part "TEST_PT"))
    )
    (comp (ref "TP15")
      (value "TEST_PT")
      (footprint "TEST_PT_SMD")
      (libsource (lib "Henry1_20_2010") (part "TEST_PT"))
    )
    (comp (ref "TP16")
      (value "TEST_PT")
      (footprint "TEST_PT_SMD")
      (libsource (lib "Henry1_20_2010") (part "TEST_PT"))
    )
    (comp (ref "TP17")
      (value "TEST_PT")
      (footprint "TEST_PT_SMD")
      (libsource (lib "Henry1_20_2010") (part "TEST_PT"))
    )
    (comp (ref "TP18")
      (value "TEST_PT")
      (footprint "TEST_PT_SMD")
      (libsource (lib "Henry1_20_2010") (part "TEST_PT"))
    )
    (comp (ref "TP19")
      (value "TEST_PT")
      (footprint "TEST_PT_SMD")
      (libsource (lib "Henry1_20_2010") (part "TEST_PT"))
    )
    (comp (ref "TP20")
      (value "TEST_PT")
      (footprint "TEST_PT_SMD")
      (libsource (lib "Henry1_20_2010") (part "TEST_PT"))
    )
    (comp (ref "TP21")
      (value "TEST_PT")
      (footprint "TEST_PT_SMD")
      (libsource (lib "Henry1_20_2010") (part "TEST_PT"))
    )
    (comp (ref "TP22")
      (value "TEST_PT")
      (footprint "TEST_PT_SMD")
      (libsource (lib "Henry1_20_2010") (part "TEST_PT"))
    )
    (comp (ref "TP23")
      (value "TEST_PT")
      (footprint "TEST_PT_SMD")
      (libsource (lib "Henry1_20_2010") (part "TEST_PT"))
    )
    (comp (ref "TP24")
      (value "TEST_PT")
      (footprint "TEST_PT_SMD")
      (libsource (lib "Henry1_20_2010") (part "TEST_PT"))
    )
    (comp (ref "TP25")
      (value "TEST_PT")
      (footprint "TEST_PT_SMD")
      (libsource (lib "Henry1_20_2010") (part "TEST_PT"))
    )
    (comp (ref "TP26")
      (value "TEST_PT")
      (footprint "TEST_PT_SMD")
      (libsource (lib "Henry1_20_2010") (part "TEST_PT"))
    )
    (comp (ref "TP27")
      (value "TEST_PT")
      (footprint "TEST_PT_SMD")
      (libsource (lib "Henry1_20_2010") (part "TEST_PT"))
    )
    (comp (ref "TP28")
      (value "TEST_PT")
      (footprint "TEST_PT_SMD")
      (libsource (lib "Henry1_20_2010") (part "TEST_PT"))
    )
    (comp (ref "TP29")
      (value "TEST_PT")
      (footprint "TEST_PT_SMD")
      (libsource (lib "Henry1_20_2010") (part "TEST_PT"))
    )
    (comp (ref "TP30")
      (value "TEST_PT")
      (footprint "TEST_PT_SMD")
      (libsource (lib "Henry1_20_2010") (part "TEST_PT"))
    )
    (comp (ref "TP31")
      (value "TEST_PT")
      (footprint "TEST_PT_SMD")
      (libsource (lib "Henry1_20_2010") (part "TEST_PT"))
    )
    (comp (ref "TP32")
      (value "TEST_PT")
      (footprint "TEST_PT_SMD")
      (libsource (lib "Henry1_20_2010") (part "TEST_PT"))
    )
    (comp (ref "TP33")
      (value "TEST_PT")
      (footprint "TEST_PT_SMD")
      (libsource (lib "Henry1_20_2010") (part "TEST_PT"))
    )
    (comp (ref "TP34")
      (value "TEST_PT")
      (footprint "TEST_PT_SMD")
      (libsource (lib "Henry1_20_2010") (part "TEST_PT"))
    )
    (comp (ref "TP35")
      (value "TEST_PT")
      (footprint "TEST_PT_SMD")
      (libsource (lib "Henry1_20_2010") (part "TEST_PT"))
    )
    (comp (ref "TP36")
      (value "TEST_PT")
      (footprint "TEST_PT_SMD")
      (libsource (lib "Henry1_20_2010") (part "TEST_PT"))
    )
    (comp (ref "TP37")
      (value "TEST_PT")
      (footprint "TEST_PT_SMD")
      (libsource (lib "Henry1_20_2010") (part "TEST_PT"))
    )
    (comp (ref "TP38")
      (value "TEST_PT")
      (footprint "TEST_PT_SMD")
      (libsource (lib "Henry1_20_2010") (part "TEST_PT"))
    )
    (comp (ref "TP39")
      (value "TEST_PT")
      (footprint "TEST_PT_SMD")
      (libsource (lib "Henry1_20_2010") (part "TEST_PT"))
    )
    (comp (ref "TP40")
      (value "TEST_PT")
      (footprint "TEST_PT_SMD")
      (libsource (lib "Henry1_20_2010") (part "TEST_PT"))
    )
    (comp (ref "TP41")
      (value "TEST_PT")
      (footprint "TEST_PT_SMD")
      (libsource (lib "Henry1_20_2010") (part "TEST_PT"))
    )
    (comp (ref "TP42")
      (value "TEST_PT")
      (footprint "TEST_PT_SMD")
      (libsource (lib "Henry1_20_2010") (part "TEST_PT"))
    )
    (comp (ref "TP43")
      (value "TEST_PT")
      (footprint "TEST_PT_SMD")
      (libsource (lib "Henry1_20_2010") (part "TEST_PT"))
    )
    (comp (ref "TP44")
      (value "TEST_PT")
      (footprint "TEST_PT_SMD")
      (libsource (lib "Henry1_20_2010") (part "TEST_PT"))
    )
    (comp (ref "TP45")
      (value "TEST_PT")
      (footprint "TEST_PT_SMD")
      (libsource (lib "Henry1_20_2010") (part "TEST_PT"))
    )
    (comp (ref "TP46")
      (value "TEST_PT")
      (footprint "TEST_PT_SMD")
      (libsource (lib "Henry1_20_2010") (part "TEST_PT"))
    )
    (comp (ref "TP47")
      (value "TEST_PT")
      (footprint "TEST_PT_SMD")
      (libsource (lib "Henry1_20_2010") (part "TEST_PT"))
    )
    (comp (ref "TVS1")
      (value "SMAJ5.0CA")
      (footprint "D0-214AC")
      (description "TVS 400W 12V BIDIRECT SMA")
      (fields (field (name "MFRPARTNUM") "SMAJ12CA-TP"))
      (libsource (lib "FriedParts") (part "SMAJ12CA-TPMC"))
    )
    (comp (ref "U1")
      (value "STM32F407")
      (footprint "LQFP100 14x14mm")
      (description "176 pin ARM CORTEX-M4")
      (libsource (lib "PaulMartin") (part "STM32F407"))
    )
    (comp (ref "U2")
      (value "LT1790-4.096")
      (footprint "LT1790--VREF-TSOT23")
      (libsource (lib "Henry1_20_2010") (part "LT1790-Volt-Ref"))
    )
    (comp (ref "U3")
      (value "USBUF01P6")
      (footprint "USB-EMI-STM-USBUF01P6-SOT666IP")
      (libsource (lib "Henry1_20_2010") (part "USBUF01P6"))
    )
    (comp (ref "U4")
      (value "LT1790-2.048")
      (footprint "LT1790--VREF-TSOT23")
      (libsource (lib "Henry1_20_2010") (part "LT1790-Volt-Ref"))
    )
    (comp (ref "U5")
      (value "OPA336")
      (footprint "SOT23-5 -TI")
      (libsource (lib "Henry1_20_2010") (part "OPA335"))
    )
    (comp (ref "U6")
      (value "INA214")
      (footprint "SC70-6pin-TI")
      (libsource (lib "Henry1_20_2010") (part "INA21X-CurrentSenseAmp"))
    )
    (comp (ref "U7")
      (value "INA214")
      (footprint "SC70-6pin-TI")
      (libsource (lib "Henry1_20_2010") (part "INA21X-CurrentSenseAmp"))
    )
    (comp (ref "U8")
      (value "LT1377")
      (footprint "SOIC-8Pin-Linear")
      (libsource (lib "Henry1_20_2010") (part "LT1377"))
    )
    (comp (ref "U9")
      (value "LT1210")
      (footprint "DDPak-7Lead-LinearTech")
      (libsource (lib "Henry1_20_2010") (part "LT1210-OpAmp"))
    )
    (comp (ref "U10")
      (value "INA214")
      (footprint "SC70-6pin-TI")
      (libsource (lib "Henry1_20_2010") (part "INA21X-CurrentSenseAmp"))
    )
    (comp (ref "U11")
      (value "INA214")
      (footprint "SC70-6pin-TI")
      (libsource (lib "Henry1_20_2010") (part "INA21X-CurrentSenseAmp"))
    )
    (comp (ref "U12")
      (value "LT1175")
      (footprint "SOT223-3Lead-STPackage-LinearTechLT1129-3.3")
      (libsource (lib "Henry1_20_2010") (part "LT1175"))
    )
    (comp (ref "U13")
      (value "INA214")
      (footprint "SC70-6pin-TI")
      (libsource (lib "Henry1_20_2010") (part "INA21X-CurrentSenseAmp"))
    )
    (comp (ref "U14")
      (value "INA214")
      (footprint "SC70-6pin-TI")
      (libsource (lib "Henry1_20_2010") (part "INA21X-CurrentSenseAmp"))
    )
    (comp (ref "U15")
      (value "LT1129-5")
      (footprint "SOT223-3Lead-STPackage-LinearTechLT1129-3.3")
      (libsource (lib "Henry1_20_2010") (part "LT1129-5"))
    )
    (comp (ref "U16")
      (value "LT1377")
      (footprint "SOIC-8Pin-Linear")
      (libsource (lib "Henry1_20_2010") (part "LT1377"))
    )
    (comp (ref "U17")
      (value "INA214")
      (footprint "SC70-6pin-TI")
      (libsource (lib "Henry1_20_2010") (part "INA21X-CurrentSenseAmp"))
    )
    (comp (ref "U18")
      (value "INA214")
      (footprint "SC70-6pin-TI")
      (libsource (lib "Henry1_20_2010") (part "INA21X-CurrentSenseAmp"))
    )
    (comp (ref "U19")
      (value "INA214")
      (footprint "SC70-6pin-TI")
      (libsource (lib "Henry1_20_2010") (part "INA21X-CurrentSenseAmp"))
    )
    (comp (ref "U20")
      (value "INA214")
      (footprint "SC70-6pin-TI")
      (libsource (lib "Henry1_20_2010") (part "INA21X-CurrentSenseAmp"))
    )
    (comp (ref "U21")
      (value "MCP1603L")
      (footprint "TSOT-5Lead-MCP1603/B/L")
      (libsource (lib "Henry1_20_2010") (part "MCP1603L"))
    )
    (comp (ref "U22")
      (value "INA214")
      (footprint "SC70-6pin-TI")
      (libsource (lib "Henry1_20_2010") (part "INA21X-CurrentSenseAmp"))
    )
    (comp (ref "U23")
      (value "INA214")
      (footprint "SC70-6pin-TI")
      (libsource (lib "Henry1_20_2010") (part "INA21X-CurrentSenseAmp"))
    )
    (comp (ref "U24")
      (value "INA214")
      (footprint "SC70-6pin-TI")
      (libsource (lib "Henry1_20_2010") (part "INA21X-CurrentSenseAmp"))
    )
    (comp (ref "U25")
      (value "INA214")
      (footprint "SC70-6pin-TI")
      (libsource (lib "Henry1_20_2010") (part "INA21X-CurrentSenseAmp"))
    )
    (comp (ref "U26")
      (value "INA214")
      (footprint "SC70-6pin-TI")
      (libsource (lib "Henry1_20_2010") (part "INA21X-CurrentSenseAmp"))
    )
    (comp (ref "USB")
      (value "USB MiniB")
      (footprint "USB-MINIB")
      (description "Mini USB")
      (fields (field (name "PUBLISHER") "Altium Limited"))
      (libsource (lib "Henry1_20_2010") (part "USB MiniB"))
    )
    (comp (ref "VPWR1")
      (value "TERM BLOCK 2POS")
      (footprint "Conn-ScrewTerminal-2pin-Phoenix")
      (libsource (lib "Henry1_20_2010") (part "2Pin-PhoenixTerminalBlock"))
    )
    (comp (ref "X1")
      (value "XTAL-ABMM")
      (footprint "ABMM-Crystal")
      (fields (field (name "ALTIUM_VALUE") "8MHz"))
      (libsource (lib "Henry1_20_2010") (part "XTAL-ABMM"))
    )
  )
  (nets
    (net (code "1") (name "+5V") (class "Default")
      (node (ref "C12") (pin "2") (pinfunction "2_2") (pintype "passive"))
      (node (ref "C15") (pin "2") (pinfunction "2_2") (pintype "passive"))
      (node (ref "C20") (pin "2") (pinfunction "2_2") (pintype "passive"))
      (node (ref "C21") (pin "2") (pinfunction "2_2") (pintype "passive"))
      (node (ref "C23") (pin "2") (pinfunction "2_2") (pintype "passive"))
      (node (ref "C24") (pin "2") (pinfunction "2_2") (pintype "passive"))
      (node (ref "C28") (pin "2") (pinfunction "2_2") (pintype "passive"))
      (node (ref "C29") (pin "2") (pinfunction "2_2") (pintype "passive"))
      (node (ref "C33") (pin "2") (pinfunction "2_2") (pintype "passive"))
      (node (ref "C34") (pin "2") (pinfunction "2_2") (pintype "passive"))
      (node (ref "C38") (pin "2") (pinfunction "2_2") (pintype "passive"))
      (node (ref "C40") (pin "2") (pinfunction "2_2") (pintype "passive"))
      (node (ref "C41") (pin "2") (pinfunction "2_2") (pintype "passive"))
      (node (ref "C44") (pin "2") (pinfunction "2_2") (pintype "passive"))
      (node (ref "C45") (pin "2") (pinfunction "2_2") (pintype "passive"))
      (node (ref "C46") (pin "2") (pinfunction "2_2") (pintype "passive"))
      (node (ref "C47") (pin "2") (pinfunction "2_2") (pintype "passive"))
      (node (ref "C49") (pin "2") (pinfunction "2_2") (pintype "passive"))
      (node (ref "C50") (pin "2") (pinfunction "2_2") (pintype "passive"))
      (node (ref "C52") (pin "2") (pinfunction "2_2") (pintype "passive"))
      (node (ref "R23") (pin "2") (pinfunction "2_2") (pintype "passive"))
      (node (ref "R32") (pin "2") (pinfunction "2_2") (pintype "passive"))
      (node (ref "U10") (pin "3") (pinfunction "V+_3") (pintype "passive"))
      (node (ref "U11") (pin "3") (pinfunction "V+_3") (pintype "passive"))
      (node (ref "U13") (pin "3") (pinfunction "V+_3") (pintype "passive"))
      (node (ref "U14") (pin "3") (pinfunction "V+_3") (pintype "passive"))
      (node (ref "U15") (pin "3") (pinfunction "OUT_3") (pintype "passive"))
      (node (ref "U17") (pin "3") (pinfunction "V+_3") (pintype "passive"))
      (node (ref "U18") (pin "3") (pinfunction "V+_3") (pintype "passive"))
      (node (ref "U19") (pin "3") (pinfunction "V+_3") (pintype "passive"))
      (node (ref "U2") (pin "4") (pinfunction "VIN_4") (pintype "passive"))
      (node (ref "U20") (pin "3") (pinfunction "V+_3") (pintype "passive"))
      (node (ref "U22") (pin "3") (pinfunction "V+_3") (pintype "passive"))
      (node (ref "U23") (pin "3") (pinfunction "V+_3") (pintype "passive"))
      (node (ref "U24") (pin "3") (pinfunction "V+_3") (pintype "passive"))
      (node (ref "U25") (pin "3") (pinfunction "V+_3") (pintype "passive"))
      (node (ref "U26") (pin "3") (pinfunction "V+_3") (pintype "passive"))
      (node (ref "U4") (pin "4") (pinfunction "VIN_4") (pintype "passive"))
      (node (ref "U6") (pin "3") (pinfunction "V+_3") (pintype "passive"))
      (node (ref "U7") (pin "3") (pinfunction "V+_3") (pintype "passive"))
      (node (ref "U9") (pin "4") (pinfunction "V+_4") (pintype "passive"))
      (node (ref "U9") (pin "8") (pinfunction "PAD_8") (pintype "passive"))
    )
    (net (code "2") (name "+6V") (class "Default")
      (node (ref "C39") (pin "2") (pinfunction "2_2") (pintype "passive"))
      (node (ref "D12") (pin "C") (pinfunction "C_C") (pintype "passive"))
      (node (ref "D2") (pin "1") (pinfunction "A_1") (pintype "passive"))
      (node (ref "R38") (pin "1") (pinfunction "1_1") (pintype "passive"))
      (node (ref "U15") (pin "1") (pinfunction "VIN_1") (pintype "passive"))
    )
    (net (code "3") (name "-5V") (class "Default")
      (node (ref "C26") (pin "1") (pinfunction "1_1") (pintype "passive"))
      (node (ref "C35") (pin "2") (pinfunction "2_2") (pintype "passive"))
      (node (ref "C36") (pin "2") (pinfunction "2_2") (pintype "passive"))
      (node (ref "R26") (pin "2") (pinfunction "2_2") (pintype "passive"))
      (node (ref "U12") (pin "1") (pinfunction "Vout_1") (pintype "passive"))
      (node (ref "U9") (pin "6") (pinfunction "V-_6") (pintype "passive"))
    )
    (net (code "4") (name "-6V") (class "Default")
      (node (ref "C25") (pin "2") (pinfunction "2_2") (pintype "passive"))
      (node (ref "D10") (pin "A") (pinfunction "A_A") (pintype "passive"))
      (node (ref "R1") (pin "1") (pinfunction "1_1") (pintype "passive"))
      (node (ref "R25") (pin "1") (pinfunction "1_1") (pintype "passive"))
      (node (ref "U12") (pin "2") (pinfunction "Vin_2") (pintype "passive"))
      (node (ref "U12") (pin "4") (pinfunction "TAB/Vin_4") (pintype "passive"))
    )
    (net (code "5") (name "/AIN0") (class "Default")
      (node (ref "TP25") (pin "1") (pinfunction "TP?_1") (pintype "passive"))
      (node (ref "U1") (pin "23") (pinfunction "PA0_23") (pintype "passive"))
      (node (ref "U6") (pin "6") (pinfunction "OUT_6") (pintype "passive"))
    )
    (net (code "6") (name "/AIN1") (class "Default")
      (node (ref "TP30") (pin "1") (pinfunction "TP?_1") (pintype "passive"))
      (node (ref "U1") (pin "24") (pinfunction "PA1_24") (pintype "passive"))
      (node (ref "U10") (pin "6") (pinfunction "OUT_6") (pintype "passive"))
    )
    (net (code "7") (name "/AIN2") (class "Default")
      (node (ref "TP32") (pin "1") (pinfunction "TP?_1") (pintype "passive"))
      (node (ref "U1") (pin "25") (pinfunction "PA2_25") (pintype "passive"))
      (node (ref "U13") (pin "6") (pinfunction "OUT_6") (pintype "passive"))
    )
    (net (code "8") (name "/AIN3") (class "Default")
      (node (ref "TP34") (pin "1") (pinfunction "TP?_1") (pintype "passive"))
      (node (ref "U1") (pin "26") (pinfunction "PA3_26") (pintype "passive"))
      (node (ref "U17") (pin "6") (pinfunction "OUT_6") (pintype "passive"))
    )
    (net (code "9") (name "/AIN5") (class "Default")
      (node (ref "TP36") (pin "1") (pinfunction "TP?_1") (pintype "passive"))
      (node (ref "U1") (pin "30") (pinfunction "PA5_30") (pintype "passive"))
      (node (ref "U19") (pin "6") (pinfunction "OUT_6") (pintype "passive"))
    )
    (net (code "10") (name "/AIN6") (class "Default")
      (node (ref "TP38") (pin "1") (pinfunction "TP?_1") (pintype "passive"))
      (node (ref "U1") (pin "31") (pinfunction "PA6_31") (pintype "passive"))
      (node (ref "U22") (pin "6") (pinfunction "OUT_6") (pintype "passive"))
    )
    (net (code "11") (name "/AIN7") (class "Default")
      (node (ref "TP40") (pin "1") (pinfunction "TP?_1") (pintype "passive"))
      (node (ref "U1") (pin "32") (pinfunction "PA7_32") (pintype "passive"))
      (node (ref "U24") (pin "6") (pinfunction "OUT_6") (pintype "passive"))
    )
    (net (code "12") (name "/AIN8") (class "Default")
      (node (ref "TP43") (pin "1") (pinfunction "TP?_1") (pintype "passive"))
      (node (ref "U1") (pin "35") (pinfunction "PB0_35") (pintype "passive"))
      (node (ref "U26") (pin "6") (pinfunction "OUT_6") (pintype "passive"))
    )
    (net (code "13") (name "/AIN9") (class "Default")
      (node (ref "TP26") (pin "1") (pinfunction "TP?_1") (pintype "passive"))
      (node (ref "U1") (pin "36") (pinfunction "PB1_36") (pintype "passive"))
      (node (ref "U7") (pin "6") (pinfunction "OUT_6") (pintype "passive"))
    )
    (net (code "14") (name "/AIN10") (class "Default")
      (node (ref "TP31") (pin "1") (pinfunction "TP?_1") (pintype "passive"))
      (node (ref "U1") (pin "15") (pinfunction "PC0_15") (pintype "passive"))
      (node (ref "U11") (pin "6") (pinfunction "OUT_6") (pintype "passive"))
    )
    (net (code "15") (name "/AIN11") (class "Default")
      (node (ref "TP33") (pin "1") (pinfunction "TP?_1") (pintype "passive"))
      (node (ref "U1") (pin "16") (pinfunction "PC1_16") (pintype "passive"))
      (node (ref "U14") (pin "6") (pinfunction "OUT_6") (pintype "passive"))
    )
    (net (code "16") (name "/AIN12") (class "Default")
      (node (ref "TP35") (pin "1") (pinfunction "TP?_1") (pintype "passive"))
      (node (ref "U1") (pin "17") (pinfunction "PC2_17") (pintype "passive"))
      (node (ref "U18") (pin "6") (pinfunction "OUT_6") (pintype "passive"))
    )
    (net (code "17") (name "/AIN13") (class "Default")
      (node (ref "TP37") (pin "1") (pinfunction "TP?_1") (pintype "passive"))
      (node (ref "U1") (pin "18") (pinfunction "PC3_18") (pintype "passive"))
      (node (ref "U20") (pin "6") (pinfunction "OUT_6") (pintype "passive"))
    )
    (net (code "18") (name "/AIN14") (class "Default")
      (node (ref "TP39") (pin "1") (pinfunction "TP?_1") (pintype "passive"))
      (node (ref "U1") (pin "33") (pinfunction "PC4_33") (pintype "passive"))
      (node (ref "U23") (pin "6") (pinfunction "OUT_6") (pintype "passive"))
    )
    (net (code "19") (name "/AIN15") (class "Default")
      (node (ref "TP41") (pin "1") (pinfunction "TP?_1") (pintype "passive"))
      (node (ref "U1") (pin "34") (pinfunction "PC5_34") (pintype "passive"))
      (node (ref "U25") (pin "6") (pinfunction "OUT_6") (pintype "passive"))
    )
    (net (code "20") (name "/AMP_SD") (class "Default")
      (node (ref "Q1") (pin "1") (pinfunction "D_1") (pintype "passive"))
      (node (ref "R32") (pin "1") (pinfunction "1_1") (pintype "passive"))
      (node (ref "U9") (pin "3") (pinfunction "~{SD}_3") (pintype "passive"))
    )
    (net (code "21") (name "/AMP_SD_CTRL") (class "Default")
      (node (ref "Q1") (pin "2") (pinfunction "G_2") (pintype "passive"))
      (node (ref "U1") (pin "58") (pinfunction "PD11_58") (pintype "passive"))
    )
    (net (code "22") (name "/BOOT0") (class "Default")
      (node (ref "JMP1") (pin "1") (pinfunction "1_1") (pintype "passive"))
      (node (ref "R5") (pin "1") (pinfunction "1_1") (pintype "passive"))
      (node (ref "U1") (pin "94") (pinfunction "BOOT0_94") (pintype "passive"))
    )
    (net (code "23") (name "/BOOT1") (class "Default")
      (node (ref "CON1") (pin "17") (pinfunction "17_17") (pintype "passive"))
      (node (ref "JO1") (pin "1") (pinfunction "1_1") (pintype "passive"))
      (node (ref "R6") (pin "2") (pinfunction "2_2") (pintype "passive"))
      (node (ref "U1") (pin "37") (pinfunction "PB2_37") (pintype "passive"))
    )
    (net (code "24") (name "/D+") (class "Default")
      (node (ref "U3") (pin "6") (pinfunction "D4_6") (pintype "passive"))
      (node (ref "USB") (pin "3") (pinfunction "D+_3") (pintype "power_in"))
    )
    (net (code "25") (name "/D-") (class "Default")
      (node (ref "U3") (pin "4") (pinfunction "D3_4") (pintype "passive"))
      (node (ref "USB") (pin "2") (pinfunction "D-_2") (pintype "power_in"))
    )
    (net (code "26") (name "/ELEC0") (class "Default")
      (node (ref "CON3") (pin "2") (pinfunction "2_2") (pintype "passive"))
      (node (ref "R18") (pin "1") (pinfunction "1_1") (pintype "passive"))
      (node (ref "TP23") (pin "1") (pinfunction "TP?_1") (pintype "passive"))
      (node (ref "U6") (pin "4") (pinfunction "VIN+_4") (pintype "passive"))
    )
    (net (code "27") (name "/ELEC1") (class "Default")
      (node (ref "CON3") (pin "4") (pinfunction "4_4") (pintype "passive"))
      (node (ref "R21") (pin "1") (pinfunction "1_1") (pintype "passive"))
      (node (ref "U10") (pin "4") (pinfunction "VIN+_4") (pintype "passive"))
    )
    (net (code "28") (name "/ELEC2") (class "Default")
      (node (ref "CON3") (pin "6") (pinfunction "6_6") (pintype "passive"))
      (node (ref "R29") (pin "1") (pinfunction "1_1") (pintype "passive"))
      (node (ref "U13") (pin "4") (pinfunction "VIN+_4") (pintype "passive"))
    )
    (net (code "29") (name "/ELEC3") (class "Default")
      (node (ref "CON3") (pin "8") (pinfunction "8_8") (pintype "passive"))
      (node (ref "R34") (pin "1") (pinfunction "1_1") (pintype "passive"))
      (node (ref "U17") (pin "4") (pinfunction "VIN+_4") (pintype "passive"))
    )
    (net (code "30") (name "/ELEC5") (class "Default")
      (node (ref "CON3") (pin "10") (pinfunction "10_10") (pintype "passive"))
      (node (ref "R40") (pin "1") (pinfunction "1_1") (pintype "passive"))
      (node (ref "U19") (pin "4") (pinfunction "VIN+_4") (pintype "passive"))
    )
    (net (code "31") (name "/ELEC6") (class "Default")
      (node (ref "CON3") (pin "12") (pinfunction "12_12") (pintype "passive"))
      (node (ref "R43") (pin "1") (pinfunction "1_1") (pintype "passive"))
      (node (ref "U22") (pin "4") (pinfunction "VIN+_4") (pintype "passive"))
    )
    (net (code "32") (name "/ELEC7") (class "Default")
      (node (ref "CON3") (pin "14") (pinfunction "14_14") (pintype "passive"))
      (node (ref "R45") (pin "1") (pinfunction "1_1") (pintype "passive"))
      (node (ref "U24") (pin "4") (pinfunction "VIN+_4") (pintype "passive"))
    )
    (net (code "33") (name "/ELEC8") (class "Default")
      (node (ref "CON3") (pin "16") (pinfunction "16_16") (pintype "passive"))
      (node (ref "R47") (pin "1") (pinfunction "1_1") (pintype "passive"))
      (node (ref "U26") (pin "4") (pinfunction "VIN+_4") (pintype "passive"))
    )
    (net (code "34") (name "/ELEC9") (class "Default")
      (node (ref "CON3") (pin "18") (pinfunction "18_18") (pintype "passive"))
      (node (ref "R19") (pin "1") (pinfunction "1_1") (pintype "passive"))
      (node (ref "U7") (pin "4") (pinfunction "VIN+_4") (pintype "passive"))
    )
    (net (code "35") (name "/ELEC10") (class "Default")
      (node (ref "CON3") (pin "20") (pinfunction "20_20") (pintype "passive"))
      (node (ref "R22") (pin "1") (pinfunction "1_1") (pintype "passive"))
      (node (ref "U11") (pin "4") (pinfunction "VIN+_4") (pintype "passive"))
    )
    (net (code "36") (name "/ELEC11") (class "Default")
      (node (ref "CON3") (pin "22") (pinfunction "22_22") (pintype "passive"))
      (node (ref "R30") (pin "1") (pinfunction "1_1") (pintype "passive"))
      (node (ref "U14") (pin "4") (pinfunction "VIN+_4") (pintype "passive"))
    )
    (net (code "37") (name "/ELEC12") (class "Default")
      (node (ref "CON3") (pin "24") (pinfunction "24_24") (pintype "passive"))
      (node (ref "R35") (pin "1") (pinfunction "1_1") (pintype "passive"))
      (node (ref "U18") (pin "4") (pinfunction "VIN+_4") (pintype "passive"))
    )
    (net (code "38") (name "/ELEC13") (class "Default")
      (node (ref "CON3") (pin "26") (pinfunction "26_26") (pintype "passive"))
      (node (ref "R41") (pin "1") (pinfunction "1_1") (pintype "passive"))
      (node (ref "U20") (pin "4") (pinfunction "VIN+_4") (pintype "passive"))
    )
    (net (code "39") (name "/ELEC14") (class "Default")
      (node (ref "CON3") (pin "28") (pinfunction "28_28") (pintype "passive"))
      (node (ref "R44") (pin "1") (pinfunction "1_1") (pintype "passive"))
      (node (ref "U23") (pin "4") (pinfunction "VIN+_4") (pintype "passive"))
    )
    (net (code "40") (name "/ELEC15") (class "Default")
      (node (ref "CON3") (pin "30") (pinfunction "30_30") (pintype "passive"))
      (node (ref "R46") (pin "1") (pinfunction "1_1") (pintype "passive"))
      (node (ref "U25") (pin "4") (pinfunction "VIN+_4") (pintype "passive"))
    )
    (net (code "41") (name "/HALFREF") (class "Default")
      (node (ref "U10") (pin "1") (pinfunction "REF_1") (pintype "passive"))
      (node (ref "U11") (pin "1") (pinfunction "REF_1") (pintype "passive"))
      (node (ref "U13") (pin "1") (pinfunction "REF_1") (pintype "passive"))
      (node (ref "U14") (pin "1") (pinfunction "REF_1") (pintype "passive"))
      (node (ref "U17") (pin "1") (pinfunction "REF_1") (pintype "passive"))
      (node (ref "U18") (pin "1") (pinfunction "REF_1") (pintype "passive"))
      (node (ref "U19") (pin "1") (pinfunction "REF_1") (pintype "passive"))
      (node (ref "U20") (pin "1") (pinfunction "REF_1") (pintype "passive"))
      (node (ref "U22") (pin "1") (pinfunction "REF_1") (pintype "passive"))
      (node (ref "U23") (pin "1") (pinfunction "REF_1") (pintype "passive"))
      (node (ref "U24") (pin "1") (pinfunction "REF_1") (pintype "passive"))
      (node (ref "U25") (pin "1") (pinfunction "REF_1") (pintype "passive"))
      (node (ref "U26") (pin "1") (pinfunction "REF_1") (pintype "passive"))
      (node (ref "U5") (pin "1") (pinfunction "OUT_1") (pintype "passive"))
      (node (ref "U5") (pin "4") (pinfunction "IN-_4") (pintype "passive"))
      (node (ref "U6") (pin "1") (pinfunction "REF_1") (pintype "passive"))
      (node (ref "U7") (pin "1") (pinfunction "REF_1") (pintype "passive"))
    )
    (net (code "42") (name "/LED_B") (class "Default")
      (node (ref "D4") (pin "1") (pinfunction "A_1") (pintype "passive"))
      (node (ref "U1") (pin "62") (pinfunction "PD15_62") (pintype "passive"))
    )
    (net (code "43") (name "/LED_G") (class "Default")
      (node (ref "D6") (pin "1") (pinfunction "A_1") (pintype "passive"))
      (node (ref "U1") (pin "59") (pinfunction "PD12_59") (pintype "passive"))
    )
    (net (code "44") (name "/LED_O") (class "Default")
      (node (ref "D3") (pin "1") (pinfunction "A_1") (pintype "passive"))
      (node (ref "U1") (pin "60") (pinfunction "PD13_60") (pintype "passive"))
    )
    (net (code "45") (name "/LED_R") (class "Default")
      (node (ref "D5") (pin "1") (pinfunction "A_1") (pintype "passive"))
      (node (ref "U1") (pin "61") (pinfunction "PD14_61") (pintype "passive"))
    )
    (net (code "46") (name "/NRST") (class "Default")
      (node (ref "C10") (pin "2") (pinfunction "2_2") (pintype "passive"))
      (node (ref "CN2") (pin "5") (pinfunction "NRST_5") (pintype "passive"))
      (node (ref "R2") (pin "1") (pinfunction "1_1") (pintype "passive"))
      (node (ref "RST1") (pin "3") (pinfunction "3_3") (pintype "passive"))
      (node (ref "RST1") (pin "4") (pinfunction "4_4") (pintype "passive"))
      (node (ref "U1") (pin "14") (pinfunction "NRST_14") (pintype "passive"))
    )
    (net (code "47") (name "/OSC_IN") (class "Default")
      (node (ref "C13") (pin "2") (pinfunction "2_2") (pintype "passive"))
      (node (ref "U1") (pin "12") (pinfunction "PH0_12") (pintype "passive"))
      (node (ref "X1") (pin "3") (pinfunction "3_3") (pintype "passive"))
    )
    (net (code "48") (name "/OSC_OUT") (class "Default")
      (node (ref "C16") (pin "1") (pinfunction "1_1") (pintype "passive"))
      (node (ref "U1") (pin "13") (pinfunction "PH1_13") (pintype "passive"))
      (node (ref "X1") (pin "1") (pinfunction "1_1") (pintype "passive"))
    )
    (net (code "49") (name "/PA8") (class "Default")
      (node (ref "TP16") (pin "1") (pinfunction "TP?_1") (pintype "passive"))
      (node (ref "U1") (pin "67") (pinfunction "PA8_67") (pintype "passive"))
    )
    (net (code "50") (name "/PA10{slash}USART1_RX{slash}USB_ID") (class "Default")
      (node (ref "JO3") (pin "1") (pinfunction "1_1") (pintype "passive"))
      (node (ref "R12") (pin "1") (pinfunction "1_1") (pintype "passive"))
      (node (ref "U1") (pin "69") (pinfunction "PA10_69") (pintype "passive"))
    )
    (net (code "51") (name "/PA13{slash}JTMS") (class "Default")
      (node (ref "CN2") (pin "4") (pinfunction "JTMS_4") (pintype "passive"))
      (node (ref "U1") (pin "72") (pinfunction "PA13_72") (pintype "passive"))
    )
    (net (code "52") (name "/PA14{slash}JTCK") (class "Default")
      (node (ref "CN2") (pin "2") (pinfunction "JTCK_2") (pintype "passive"))
      (node (ref "U1") (pin "76") (pinfunction "PA14_76") (pintype "passive"))
    )
    (net (code "53") (name "/PA15{slash}JTDI") (class "Default")
      (node (ref "TP46") (pin "1") (pinfunction "TP?_1") (pintype "passive"))
      (node (ref "U1") (pin "77") (pinfunction "PA15_77") (pintype "passive"))
    )
    (net (code "54") (name "/PB3{slash}JTDO") (class "Default")
      (node (ref "CN2") (pin "6") (pinfunction "SWO_6") (pintype "passive"))
      (node (ref "U1") (pin "89") (pinfunction "PB3_89") (pintype "passive"))
    )
    (net (code "55") (name "/PB4{slash}NJTRST") (class "Default")
      (node (ref "U1") (pin "90") (pinfunction "PB4_90") (pintype "passive"))
    )
    (net (code "56") (name "/PB05{slash}CAN2_RX") (class "Default")
      (node (ref "R16") (pin "1") (pinfunction "1_1") (pintype "passive"))
      (node (ref "U1") (pin "91") (pinfunction "PB5_91") (pintype "passive"))
    )
    (net (code "57") (name "/PB10") (class "Default")
      (node (ref "CON1") (pin "2") (pinfunction "2_2") (pintype "passive"))
      (node (ref "U1") (pin "47") (pinfunction "PB10_47") (pintype "passive"))
    )
    (net (code "58") (name "/PB11{slash}USART3_RX") (class "Default")
      (node (ref "R15") (pin "1") (pinfunction "1_1") (pintype "passive"))
      (node (ref "U1") (pin "48") (pinfunction "PB11_48") (pintype "passive"))
    )
    (net (code "59") (name "/PB12") (class "Default")
      (node (ref "CON1") (pin "18") (pinfunction "18_18") (pintype "passive"))
      (node (ref "U1") (pin "51") (pinfunction "PB12_51") (pintype "passive"))
    )
    (net (code "60") (name "/PB13") (class "Default")
      (node (ref "CON1") (pin "20") (pinfunction "20_20") (pintype "passive"))
      (node (ref "U1") (pin "52") (pinfunction "PB13_52") (pintype "passive"))
    )
    (net (code "61") (name "/PB14") (class "Default")
      (node (ref "CON1") (pin "22") (pinfunction "22_22") (pintype "passive"))
      (node (ref "U1") (pin "53") (pinfunction "PB14_53") (pintype "passive"))
    )
    (net (code "62") (name "/PB15") (class "Default")
      (node (ref "U1") (pin "54") (pinfunction "PB15_54") (pintype "passive"))
    )
    (net (code "63") (name "/PC6") (class "Default")
      (node (ref "TP20") (pin "1") (pinfunction "TP?_1") (pintype "passive"))
      (node (ref "U1") (pin "63") (pinfunction "PC6_63") (pintype "passive"))
    )
    (net (code "64") (name "/PC7") (class "Default")
      (node (ref "TP19") (pin "1") (pinfunction "TP?_1") (pintype "passive"))
      (node (ref "U1") (pin "64") (pinfunction "PC7_64") (pintype "passive"))
    )
    (net (code "65") (name "/PC8") (class "Default")
      (node (ref "TP18") (pin "1") (pinfunction "TP?_1") (pintype "passive"))
      (node (ref "U1") (pin "65") (pinfunction "PC8_65") (pintype "passive"))
    )
    (net (code "66") (name "/PC9") (class "Default")
      (node (ref "TP17") (pin "1") (pinfunction "TP?_1") (pintype "passive"))
      (node (ref "U1") (pin "66") (pinfunction "PC9_66") (pintype "passive"))
    )
    (net (code "67") (name "/PC11{slash}USART3_RX") (class "Default")
      (node (ref "R14") (pin "1") (pinfunction "1_1") (pintype "passive"))
      (node (ref "U1") (pin "79") (pinfunction "PC11_79") (pintype "passive"))
    )
    (net (code "68") (name "/PC13") (class "Default")
      (node (ref "CON1") (pin "11") (pinfunction "11_11") (pintype "passive"))
      (node (ref "U1") (pin "7") (pinfunction "PC13_7") (pintype "passive"))
    )
    (net (code "69") (name "/PC14") (class "Default")
      (node (ref "CON1") (pin "13") (pinfunction "13_13") (pintype "passive"))
      (node (ref "U1") (pin "8") (pinfunction "PC14_8") (pintype "passive"))
    )
    (net (code "70") (name "/PC15") (class "Default")
      (node (ref "CON1") (pin "15") (pinfunction "15_15") (pintype "passive"))
      (node (ref "U1") (pin "9") (pinfunction "PC15_9") (pintype "passive"))
    )
    (net (code "71") (name "/PD8") (class "Default")
      (node (ref "TP22") (pin "1") (pinfunction "TP?_1") (pintype "passive"))
      (node (ref "U1") (pin "55") (pinfunction "PD8_55") (pintype "passive"))
    )
    (net (code "72") (name "/PD9") (class "Default")
      (node (ref "TP21") (pin "1") (pinfunction "TP?_1") (pintype "passive"))
      (node (ref "U1") (pin "56") (pinfunction "PD9_56") (pintype "passive"))
    )
    (net (code "73") (name "/PE2") (class "Default")
      (node (ref "CON1") (pin "1") (pinfunction "1_1") (pintype "passive"))
      (node (ref "U1") (pin "1") (pinfunction "PE2_1") (pintype "passive"))
    )
    (net (code "74") (name "/PE3") (class "Default")
      (node (ref "CON1") (pin "3") (pinfunction "3_3") (pintype "passive"))
      (node (ref "U1") (pin "2") (pinfunction "PE3_2") (pintype "passive"))
    )
    (net (code "75") (name "/PE4") (class "Default")
      (node (ref "CON1") (pin "5") (pinfunction "5_5") (pintype "passive"))
      (node (ref "U1") (pin "3") (pinfunction "PE4_3") (pintype "passive"))
    )
    (net (code "76") (name "/PE5") (class "Default")
      (node (ref "CON1") (pin "7") (pinfunction "7_7") (pintype "passive"))
      (node (ref "U1") (pin "4") (pinfunction "PE5_4") (pintype "passive"))
    )
    (net (code "77") (name "/PE6") (class "Default")
      (node (ref "CON1") (pin "9") (pinfunction "9_9") (pintype "passive"))
      (node (ref "U1") (pin "5") (pinfunction "PE6_5") (pintype "passive"))
    )
    (net (code "78") (name "/PE7") (class "Default")
      (node (ref "CON1") (pin "19") (pinfunction "19_19") (pintype "passive"))
      (node (ref "U1") (pin "38") (pinfunction "PE7_38") (pintype "passive"))
    )
    (net (code "79") (name "/PE8") (class "Default")
      (node (ref "CON1") (pin "21") (pinfunction "21_21") (pintype "passive"))
      (node (ref "U1") (pin "39") (pinfunction "PE8_39") (pintype "passive"))
    )
    (net (code "80") (name "/PE9") (class "Default")
      (node (ref "CON1") (pin "16") (pinfunction "16_16") (pintype "passive"))
      (node (ref "U1") (pin "40") (pinfunction "PE9_40") (pintype "passive"))
    )
    (net (code "81") (name "/PE10") (class "Default")
      (node (ref "CON1") (pin "14") (pinfunction "14_14") (pintype "passive"))
      (node (ref "U1") (pin "41") (pinfunction "PE10_41") (pintype "passive"))
    )
    (net (code "82") (name "/PE11") (class "Default")
      (node (ref "CON1") (pin "12") (pinfunction "12_12") (pintype "passive"))
      (node (ref "U1") (pin "42") (pinfunction "PE11_42") (pintype "passive"))
    )
    (net (code "83") (name "/PE12") (class "Default")
      (node (ref "CON1") (pin "10") (pinfunction "10_10") (pintype "passive"))
      (node (ref "U1") (pin "43") (pinfunction "PE12_43") (pintype "passive"))
    )
    (net (code "84") (name "/PE13") (class "Default")
      (node (ref "CON1") (pin "8") (pinfunction "8_8") (pintype "passive"))
      (node (ref "U1") (pin "44") (pinfunction "PE13_44") (pintype "passive"))
    )
    (net (code "85") (name "/PE14") (class "Default")
      (node (ref "CON1") (pin "6") (pinfunction "6_6") (pintype "passive"))
      (node (ref "U1") (pin "45") (pinfunction "PE15_45") (pintype "passive"))
    )
    (net (code "86") (name "/PE15") (class "Default")
      (node (ref "CON1") (pin "4") (pinfunction "4_4") (pintype "passive"))
      (node (ref "U1") (pin "46") (pinfunction "PE15_46") (pintype "passive"))
    )
    (net (code "87") (name "/SIGGEN_EN") (class "Default")
      (node (ref "R20") (pin "2") (pinfunction "2_2") (pintype "passive"))
      (node (ref "R36") (pin "2") (pinfunction "2_2") (pintype "passive"))
      (node (ref "U1") (pin "57") (pinfunction "PD10_57") (pintype "passive"))
      (node (ref "U16") (pin "4") (pinfunction "S/S_4") (pintype "passive"))
      (node (ref "U8") (pin "4") (pinfunction "S/S_4") (pintype "passive"))
    )
    (net (code "88") (name "/USB_M") (class "Default")
      (node (ref "R13") (pin "1") (pinfunction "1_1") (pintype "passive"))
      (node (ref "U1") (pin "70") (pinfunction "PA11_70") (pintype "passive"))
    )
    (net (code "89") (name "/USB_P") (class "Default")
      (node (ref "R17") (pin "2") (pinfunction "2_2") (pintype "passive"))
      (node (ref "U1") (pin "71") (pinfunction "PA12_71") (pintype "passive"))
    )
    (net (code "90") (name "/USB_VBUS") (class "Default")
      (node (ref "JO2") (pin "1") (pinfunction "1_1") (pintype "passive"))
      (node (ref "U1") (pin "68") (pinfunction "PA9_68") (pintype "passive"))
    )
    (net (code "91") (name "/VCAP_1") (class "Default")
      (node (ref "C4") (pin "2") (pinfunction "2_2") (pintype "passive"))
      (node (ref "U1") (pin "49") (pinfunction "VCAP_1_49") (pintype "passive"))
    )
    (net (code "92") (name "/VCAP_2") (class "Default")
      (node (ref "C5") (pin "2") (pinfunction "2_2") (pintype "passive"))
      (node (ref "U1") (pin "73") (pinfunction "VCAP_2_73") (pintype "passive"))
    )
    (net (code "93") (name "/VDAC1") (class "Default")
      (node (ref "C27") (pin "1") (pinfunction "1_1") (pintype "passive"))
      (node (ref "U1") (pin "29") (pinfunction "PA4_29") (pintype "passive"))
    )
    (net (code "94") (name "/VDDA") (class "Default")
      (node (ref "C17") (pin "2") (pinfunction "2_2") (pintype "passive"))
      (node (ref "L3") (pin "1") (pinfunction "1_1") (pintype "passive"))
      (node (ref "U1") (pin "22") (pinfunction "VDDA_22") (pintype "passive"))
    )
    (net (code "95") (name "/VREF+") (class "Default")
      (node (ref "C11") (pin "2") (pinfunction "2_2") (pintype "passive"))
      (node (ref "L1") (pin "1") (pinfunction "1_1") (pintype "passive"))
      (node (ref "U1") (pin "21") (pinfunction "VREF+_21") (pintype "passive"))
    )
    (net (code "96") (name "/VREF_HALF+") (class "Default")
      (node (ref "C14") (pin "2") (pinfunction "2_2") (pintype "passive"))
      (node (ref "L2") (pin "1") (pinfunction "1_1") (pintype "passive"))
      (node (ref "U5") (pin "3") (pinfunction "IN+_3") (pintype "passive"))
    )
    (net (code "97") (name "3V3") (class "Default")
      (node (ref "C1") (pin "2") (pinfunction "2_2") (pintype "passive"))
      (node (ref "C18") (pin "2") (pinfunction "2_2") (pintype "passive"))
      (node (ref "C19") (pin "2") (pinfunction "2_2") (pintype "passive"))
      (node (ref "C2") (pin "2") (pinfunction "2_2") (pintype "passive"))
      (node (ref "C3") (pin "2") (pinfunction "2_2") (pintype "passive"))
      (node (ref "C48") (pin "2") (pinfunction "2_2") (pintype "passive"))
      (node (ref "C6") (pin "2") (pinfunction "2_2") (pintype "passive"))
      (node (ref "C7") (pin "2") (pinfunction "2_2") (pintype "passive"))
      (node (ref "C8") (pin "2") (pinfunction "2_2") (pintype "passive"))
      (node (ref "C9") (pin "2") (pinfunction "2_2") (pintype "passive"))
      (node (ref "CON1") (pin "23") (pinfunction "23_23") (pintype "passive"))
      (node (ref "D1") (pin "1") (pinfunction "A_1") (pintype "passive"))
      (node (ref "JMP1") (pin "2") (pinfunction "2_2") (pintype "passive"))
      (node (ref "JO1") (pin "2") (pinfunction "2_2") (pintype "passive"))
      (node (ref "L3") (pin "2") (pinfunction "2_2") (pintype "passive"))
      (node (ref "L5") (pin "2") (pinfunction "2_2") (pintype "passive"))
      (node (ref "R12") (pin "2") (pinfunction "2_2") (pintype "passive"))
      (node (ref "R14") (pin "2") (pinfunction "2_2") (pintype "passive"))
      (node (ref "R15") (pin "2") (pinfunction "2_2") (pintype "passive"))
      (node (ref "R16") (pin "2") (pinfunction "2_2") (pintype "passive"))
      (node (ref "R2") (pin "2") (pinfunction "2_2") (pintype "passive"))
      (node (ref "R20") (pin "1") (pinfunction "1_1") (pintype "passive"))
      (node (ref "R36") (pin "1") (pinfunction "1_1") (pintype "passive"))
      (node (ref "U1") (pin "100") (pinfunction "VDD_100") (pintype "passive"))
      (node (ref "U1") (pin "11") (pinfunction "VDD_11") (pintype "passive"))
      (node (ref "U1") (pin "19") (pinfunction "VDD_19") (pintype "passive"))
      (node (ref "U1") (pin "28") (pinfunction "VDD_28") (pintype "passive"))
      (node (ref "U1") (pin "50") (pinfunction "VDD_50") (pintype "passive"))
      (node (ref "U1") (pin "6") (pinfunction "VBAT_6") (pintype "passive"))
      (node (ref "U1") (pin "75") (pinfunction "VDD_75") (pintype "passive"))
      (node (ref "U21") (pin "5") (pinfunction "VFB/VOUT_5") (pintype "passive"))
      (node (ref "U3") (pin "5") (pinfunction "3V3_5") (pintype "passive"))
      (node (ref "U5") (pin "5") (pinfunction "V+_5") (pintype "passive"))
    )
    (net (code "98") (name "GND") (class "Default")
      (node (ref "C1") (pin "1") (pinfunction "1_1") (pintype "passive"))
      (node (ref "C10") (pin "1") (pinfunction "1_1") (pintype "passive"))
      (node (ref "C11") (pin "1") (pinfunction "1_1") (pintype "passive"))
      (node (ref "C12") (pin "1") (pinfunction "1_1") (pintype "passive"))
      (node (ref "C13") (pin "1") (pinfunction "1_1") (pintype "passive"))
      (node (ref "C14") (pin "1") (pinfunction "1_1") (pintype "passive"))
      (node (ref "C15") (pin "1") (pinfunction "1_1") (pintype "passive"))
      (node (ref "C16") (pin "2") (pinfunction "2_2") (pintype "passive"))
      (node (ref "C17") (pin "1") (pinfunction "1_1") (pintype "passive"))
      (node (ref "C18") (pin "1") (pinfunction "1_1") (pintype "passive"))
      (node (ref "C19") (pin "1") (pinfunction "1_1") (pintype "passive"))
      (node (ref "C2") (pin "1") (pinfunction "1_1") (pintype "passive"))
      (node (ref "C20") (pin "1") (pinfunction "1_1") (pintype "passive"))
      (node (ref "C21") (pin "1") (pinfunction "1_1") (pintype "passive"))
      (node (ref "C22") (pin "2") (pinfunction "2_2") (pintype "passive"))
      (node (ref "C23") (pin "1") (pinfunction "1_1") (pintype "passive"))
      (node (ref "C24") (pin "1") (pinfunction "1_1") (pintype "passive"))
      (node (ref "C25") (pin "1") (pinfunction "1_1") (pintype "passive"))
      (node (ref "C26") (pin "2") (pinfunction "2_2") (pintype "passive"))
      (node (ref "C28") (pin "1") (pinfunction "1_1") (pintype "passive"))
      (node (ref "C29") (pin "1") (pinfunction "1_1") (pintype "passive"))
      (node (ref "C3") (pin "1") (pinfunction "1_1") (pintype "passive"))
      (node (ref "C31") (pin "1") (pinfunction "1_1") (pintype "passive"))
      (node (ref "C33") (pin "1") (pinfunction "1_1") (pintype "passive"))
      (node (ref "C34") (pin "1") (pinfunction "1_1") (pintype "passive"))
      (node (ref "C35") (pin "1") (pinfunction "1_1") (pintype "passive"))
      (node (ref "C36") (pin "1") (pinfunction "1_1") (pintype "passive"))
      (node (ref "C37") (pin "2") (pinfunction "2_2") (pintype "passive"))
      (node (ref "C38") (pin "1") (pinfunction "1_1") (pintype "passive"))
      (node (ref "C39") (pin "1") (pinfunction "1_1") (pintype "passive"))
      (node (ref "C4") (pin "1") (pinfunction "1_1") (pintype "passive"))
      (node (ref "C40") (pin "1") (pinfunction "1_1") (pintype "passive"))
      (node (ref "C41") (pin "1") (pinfunction "1_1") (pintype "passive"))
      (node (ref "C43") (pin "1") (pinfunction "1_1") (pintype "passive"))
      (node (ref "C44") (pin "1") (pinfunction "1_1") (pintype "passive"))
      (node (ref "C45") (pin "1") (pinfunction "1_1") (pintype "passive"))
      (node (ref "C46") (pin "1") (pinfunction "1_1") (pintype "passive"))
      (node (ref "C47") (pin "1") (pinfunction "1_1") (pintype "passive"))
      (node (ref "C48") (pin "1") (pinfunction "1_1") (pintype "passive"))
      (node (ref "C49") (pin "1") (pinfunction "1_1") (pintype "passive"))
      (node (ref "C5") (pin "1") (pinfunction "1_1") (pintype "passive"))
      (node (ref "C50") (pin "1") (pinfunction "1_1") (pintype "passive"))
      (node (ref "C51") (pin "2") (pinfunction "2_2") (pintype "passive"))
      (node (ref "C52") (pin "1") (pinfunction "1_1") (pintype "passive"))
      (node (ref "C6") (pin "1") (pinfunction "1_1") (pintype "passive"))
      (node (ref "C7") (pin "1") (pinfunction "1_1") (pintype "passive"))
      (node (ref "C8") (pin "1") (pinfunction "1_1") (pintype "passive"))
      (node (ref "C9") (pin "1") (pinfunction "1_1") (pintype "passive"))
      (node (ref "CN2") (pin "3") (pinfunction "GND_3") (pintype "passive"))
      (node (ref "CON1") (pin "24") (pinfunction "24_24") (pintype "passive"))
      (node (ref "CON2") (pin "0") (pinfunction "0_0") (pintype "passive"))
      (node (ref "CON3") (pin "1") (pinfunction "1_1") (pintype "passive"))
      (node (ref "CON3") (pin "11") (pinfunction "11_11") (pintype "passive"))
      (node (ref "CON3") (pin "13") (pinfunction "13_13") (pintype "passive"))
      (node (ref "CON3") (pin "15") (pinfunction "15_15") (pintype "passive"))
      (node (ref "CON3") (pin "17") (pinfunction "17_17") (pintype "passive"))
      (node (ref "CON3") (pin "19") (pinfunction "19_19") (pintype "passive"))
      (node (ref "CON3") (pin "21") (pinfunction "21_21") (pintype "passive"))
      (node (ref "CON3") (pin "23") (pinfunction "23_23") (pintype "passive"))
      (node (ref "CON3") (pin "25") (pinfunction "25_25") (pintype "passive"))
      (node (ref "CON3") (pin "27") (pinfunction "27_27") (pintype "passive"))
      (node (ref "CON3") (pin "29") (pinfunction "29_29") (pintype "passive"))
      (node (ref "CON3") (pin "3") (pinfunction "3_3") (pintype "passive"))
      (node (ref "CON3") (pin "31") (pinfunction "31_31") (pintype "passive"))
      (node (ref "CON3") (pin "33") (pinfunction "33_33") (pintype "passive"))
      (node (ref "CON3") (pin "34") (pinfunction "34_34") (pintype "passive"))
      (node (ref "CON3") (pin "5") (pinfunction "5_5") (pintype "passive"))
      (node (ref "CON3") (pin "7") (pinfunction "7_7") (pintype "passive"))
      (node (ref "CON3") (pin "9") (pinfunction "9_9") (pintype "passive"))
      (node (ref "CON4") (pin "1") (pintype "passive"))
      (node (ref "D7") (pin "1") (pinfunction "A_1") (pintype "passive"))
      (node (ref "L6") (pin "2") (pinfunction "2_2") (pintype "passive"))
      (node (ref "M1") (pin "0") (pinfunction "PAD_0") (pintype "power_in"))
      (node (ref "M2") (pin "0") (pinfunction "PAD_0") (pintype "power_in"))
      (node (ref "M3") (pin "0") (pinfunction "PAD_0") (pintype "power_in"))
      (node (ref "M4") (pin "0") (pinfunction "PAD_0") (pintype "power_in"))
      (node (ref "Q1") (pin "3") (pinfunction "S_3") (pintype "passive"))
      (node (ref "Q2") (pin "G") (pinfunction "G_G") (pintype "passive"))
      (node (ref "R10") (pin "1") (pinfunction "1_1") (pintype "passive"))
      (node (ref "R11") (pin "1") (pinfunction "1_1") (pintype "passive"))
      (node (ref "R18") (pin "2") (pinfunction "2_2") (pintype "passive"))
      (node (ref "R19") (pin "2") (pinfunction "2_2") (pintype "passive"))
      (node (ref "R21") (pin "2") (pinfunction "2_2") (pintype "passive"))
      (node (ref "R22") (pin "2") (pinfunction "2_2") (pintype "passive"))
      (node (ref "R28") (pin "2") (pinfunction "2_2") (pintype "passive"))
      (node (ref "R29") (pin "2") (pinfunction "2_2") (pintype "passive"))
      (node (ref "R3") (pin "2") (pinfunction "2_2") (pintype "passive"))
      (node (ref "R30") (pin "2") (pinfunction "2_2") (pintype "passive"))
      (node (ref "R31") (pin "2") (pinfunction "2_2") (pintype "passive"))
      (node (ref "R34") (pin "2") (pinfunction "2_2") (pintype "passive"))
      (node (ref "R35") (pin "2") (pinfunction "2_2") (pintype "passive"))
      (node (ref "R37") (pin "1") (pinfunction "1_1") (pintype "passive"))
      (node (ref "R39") (pin "2") (pinfunction "2_2") (pintype "passive"))
      (node (ref "R4") (pin "2") (pinfunction "2_2") (pintype "passive"))
      (node (ref "R40") (pin "2") (pinfunction "2_2") (pintype "passive"))
      (node (ref "R41") (pin "2") (pinfunction "2_2") (pintype "passive"))
      (node (ref "R42") (pin "2") (pinfunction "2_2") (pintype "passive"))
      (node (ref "R43") (pin "2") (pinfunction "2_2") (pintype "passive"))
      (node (ref "R44") (pin "2") (pinfunction "2_2") (pintype "passive"))
      (node (ref "R45") (pin "2") (pinfunction "2_2") (pintype "passive"))
      (node (ref "R46") (pin "2") (pinfunction "2_2") (pintype "passive"))
      (node (ref "R47") (pin "2") (pinfunction "2_2") (pintype "passive"))
      (node (ref "R5") (pin "2") (pinfunction "2_2") (pintype "passive"))
      (node (ref "R6") (pin "1") (pinfunction "1_1") (pintype "passive"))
      (node (ref "R7") (pin "1") (pinfunction "1_1") (pintype "passive"))
      (node (ref "R8") (pin "1") (pinfunction "1_1") (pintype "passive"))
      (node (ref "R9") (pin "1") (pinfunction "1_1") (pintype "passive"))
      (node (ref "RST1") (pin "1") (pinfunction "1_1") (pintype "passive"))
      (node (ref "RST1") (pin "2") (pinfunction "2_2") (pintype "passive"))
      (node (ref "T1") (pin "4") (pinfunction "4_4") (pintype "passive"))
      (node (ref "TP24") (pin "1") (pinfunction "TP?_1") (pintype "passive"))
      (node (ref "TP47") (pin "1") (pinfunction "TP?_1") (pintype "passive"))
      (node (ref "TVS1") (pin "C") (pinfunction "1_C") (pintype "passive"))
      (node (ref "U1") (pin "10") (pinfunction "VSS_10") (pintype "passive"))
      (node (ref "U1") (pin "20") (pinfunction "VSSA_20") (pintype "passive"))
      (node (ref "U1") (pin "27") (pinfunction "VSS_27") (pintype "passive"))
      (node (ref "U1") (pin "74") (pinfunction "VSS_74") (pintype "passive"))
      (node (ref "U1") (pin "99") (pinfunction "VSS_99") (pintype "passive"))
      (node (ref "U10") (pin "2") (pinfunction "GND_2") (pintype "passive"))
      (node (ref "U10") (pin "5") (pinfunction "VIN-_5") (pintype "passive"))
      (node (ref "U11") (pin "2") (pinfunction "GND_2") (pintype "passive"))
      (node (ref "U11") (pin "5") (pinfunction "VIN-_5") (pintype "passive"))
      (node (ref "U12") (pin "3") (pinfunction "GND_3") (pintype "passive"))
      (node (ref "U13") (pin "2") (pinfunction "GND_2") (pintype "passive"))
      (node (ref "U13") (pin "5") (pinfunction "VIN-_5") (pintype "passive"))
      (node (ref "U14") (pin "2") (pinfunction "GND_2") (pintype "passive"))
      (node (ref "U14") (pin "5") (pinfunction "VIN-_5") (pintype "passive"))
      (node (ref "U15") (pin "2") (pinfunction "GND_2") (pintype "passive"))
      (node (ref "U15") (pin "4") (pinfunction "TAB/GND_4") (pintype "passive"))
      (node (ref "U16") (pin "6") (pinfunction "GND_6") (pintype "passive"))
      (node (ref "U16") (pin "7") (pinfunction "GND_7") (pintype "passive"))
      (node (ref "U17") (pin "2") (pinfunction "GND_2") (pintype "passive"))
      (node (ref "U17") (pin "5") (pinfunction "VIN-_5") (pintype "passive"))
      (node (ref "U18") (pin "2") (pinfunction "GND_2") (pintype "passive"))
      (node (ref "U18") (pin "5") (pinfunction "VIN-_5") (pintype "passive"))
      (node (ref "U19") (pin "2") (pinfunction "GND_2") (pintype "passive"))
      (node (ref "U19") (pin "5") (pinfunction "VIN-_5") (pintype "passive"))
      (node (ref "U2") (pin "1") (pinfunction "GND_1") (pintype "passive"))
      (node (ref "U2") (pin "2") (pinfunction "GND_2") (pintype "passive"))
      (node (ref "U20") (pin "2") (pinfunction "GND_2") (pintype "passive"))
      (node (ref "U20") (pin "5") (pinfunction "VIN-_5") (pintype "passive"))
      (node (ref "U21") (pin "2") (pinfunction "GND_2") (pintype "passive"))
      (node (ref "U22") (pin "2") (pinfunction "GND_2") (pintype "passive"))
      (node (ref "U22") (pin "5") (pinfunction "VIN-_5") (pintype "passive"))
      (node (ref "U23") (pin "2") (pinfunction "GND_2") (pintype "passive"))
      (node (ref "U23") (pin "5") (pinfunction "VIN-_5") (pintype "passive"))
      (node (ref "U24") (pin "2") (pinfunction "GND_2") (pintype "passive"))
      (node (ref "U24") (pin "5") (pinfunction "VIN-_5") (pintype "passive"))
      (node (ref "U25") (pin "2") (pinfunction "GND_2") (pintype "passive"))
      (node (ref "U25") (pin "5") (pinfunction "VIN-_5") (pintype "passive"))
      (node (ref "U26") (pin "2") (pinfunction "GND_2") (pintype "passive"))
      (node (ref "U26") (pin "5") (pinfunction "VIN-_5") (pintype "passive"))
      (node (ref "U3") (pin "2") (pinfunction "GND_2") (pintype "passive"))
      (node (ref "U4") (pin "1") (pinfunction "GND_1") (pintype "passive"))
      (node (ref "U4") (pin "2") (pinfunction "GND_2") (pintype "passive"))
      (node (ref "U5") (pin "2") (pinfunction "V-_2") (pintype "passive"))
      (node (ref "U6") (pin "2") (pinfunction "GND_2") (pintype "passive"))
      (node (ref "U6") (pin "5") (pinfunction "VIN-_5") (pintype "passive"))
      (node (ref "U7") (pin "2") (pinfunction "GND_2") (pintype "passive"))
      (node (ref "U7") (pin "5") (pinfunction "VIN-_5") (pintype "passive"))
      (node (ref "U8") (pin "6") (pinfunction "GND_6") (pintype "passive"))
      (node (ref "U8") (pin "7") (pinfunction "GND_7") (pintype "passive"))
      (node (ref "USB") (pin "5") (pinfunction "GND_5") (pintype "power_in"))
      (node (ref "VPWR1") (pin "1") (pinfunction "1_1") (pintype "passive"))
      (node (ref "X1") (pin "2") (pinfunction "2_2") (pintype "passive"))
      (node (ref "X1") (pin "4") (pinfunction "4_4") (pintype "passive"))
    )
    (net (code "99") (name "Net-(C30-Pad1)") (class "Default")
      (node (ref "C30") (pin "1") (pinfunction "1_1") (pintype "passive"))
      (node (ref "R31") (pin "1") (pinfunction "1_1") (pintype "passive"))
    )
    (net (code "100") (name "Net-(C42-Pad1)") (class "Default")
      (node (ref "C42") (pin "1") (pinfunction "1_1") (pintype "passive"))
      (node (ref "R42") (pin "1") (pinfunction "1_1") (pintype "passive"))
    )
    (net (code "101") (name "Net-(CN2-VDD)") (class "Default")
      (node (ref "CN2") (pin "1") (pinfunction "VDD_1") (pintype "passive"))
      (node (ref "TP44") (pin "1") (pinfunction "TP?_1") (pintype "passive"))
    )
    (net (code "102") (name "Net-(D1-K)") (class "Default")
      (node (ref "D1") (pin "2") (pinfunction "K_2") (pintype "passive"))
      (node (ref "R3") (pin "1") (pinfunction "1_1") (pintype "passive"))
    )
    (net (code "103") (name "Net-(D2-K)") (class "Default")
      (node (ref "D2") (pin "2") (pinfunction "K_2") (pintype "passive"))
      (node (ref "R4") (pin "1") (pinfunction "1_1") (pintype "passive"))
    )
    (net (code "104") (name "Net-(D3-K)") (class "Default")
      (node (ref "D3") (pin "2") (pinfunction "K_2") (pintype "passive"))
      (node (ref "R7") (pin "2") (pinfunction "2_2") (pintype "passive"))
    )
    (net (code "105") (name "Net-(D4-K)") (class "Default")
      (node (ref "D4") (pin "2") (pinfunction "K_2") (pintype "passive"))
      (node (ref "R8") (pin "2") (pinfunction "2_2") (pintype "passive"))
    )
    (net (code "106") (name "Net-(D5-K)") (class "Default")
      (node (ref "D5") (pin "2") (pinfunction "K_2") (pintype "passive"))
      (node (ref "R9") (pin "2") (pinfunction "2_2") (pintype "passive"))
    )
    (net (code "107") (name "Net-(D6-K)") (class "Default")
      (node (ref "D6") (pin "2") (pinfunction "K_2") (pintype "passive"))
      (node (ref "R10") (pin "2") (pinfunction "2_2") (pintype "passive"))
    )
    (net (code "108") (name "Net-(D7-K)") (class "Default")
      (node (ref "D7") (pin "2") (pinfunction "K_2") (pintype "passive"))
      (node (ref "R1") (pin "2") (pinfunction "2_2") (pintype "passive"))
    )
    (net (code "109") (name "Net-(D8-K)") (class "Default")
      (node (ref "D8") (pin "2") (pinfunction "K_2") (pintype "passive"))
      (node (ref "R11") (pin "2") (pinfunction "2_2") (pintype "passive"))
    )
    (net (code "110") (name "Net-(D10-PadC)") (class "Default")
      (node (ref "D10") (pin "C") (pinfunction "C_C") (pintype "passive"))
      (node (ref "T1") (pin "2") (pinfunction "2_2") (pintype "passive"))
    )
    (net (code "111") (name "Net-(D11-PadK)") (class "Default")
      (node (ref "D11") (pin "K") (pinfunction "K_K") (pintype "passive"))
      (node (ref "D9") (pin "C") (pinfunction "C_C") (pintype "passive"))
    )
    (net (code "112") (name "Net-(F1-Pad1)") (class "Default")
      (node (ref "F1") (pin "1") (pinfunction "1_1") (pintype "passive"))
      (node (ref "S1") (pin "1") (pinfunction "1_1") (pintype "passive"))
    )
    (net (code "113") (name "Net-(S1-Pad2)") (class "Default")
      (node (ref "S1") (pin "2") (pinfunction "2_2") (pintype "passive"))
      (node (ref "VPWR1") (pin "2") (pinfunction "2_2") (pintype "passive"))
    )
    (net (code "114") (name "Net-(TP1-TP?)") (class "Default")
      (node (ref "TP1") (pin "1") (pinfunction "TP?_1") (pintype "passive"))
      (node (ref "U1") (pin "93") (pinfunction "PB7_93") (pintype "passive"))
    )
    (net (code "115") (name "Net-(TP2-TP?)") (class "Default")
      (node (ref "TP2") (pin "1") (pinfunction "TP?_1") (pintype "passive"))
      (node (ref "U1") (pin "96") (pinfunction "PB9_96") (pintype "passive"))
    )
    (net (code "116") (name "Net-(TP3-TP?)") (class "Default")
      (node (ref "TP3") (pin "1") (pinfunction "TP?_1") (pintype "passive"))
      (node (ref "U1") (pin "98") (pinfunction "PE1_98") (pintype "passive"))
    )
    (net (code "117") (name "Net-(TP4-TP?)") (class "Default")
      (node (ref "TP4") (pin "1") (pinfunction "TP?_1") (pintype "passive"))
      (node (ref "U1") (pin "92") (pinfunction "PB6_92") (pintype "passive"))
    )
    (net (code "118") (name "Net-(TP5-TP?)") (class "Default")
      (node (ref "TP5") (pin "1") (pinfunction "TP?_1") (pintype "passive"))
      (node (ref "U1") (pin "95") (pinfunction "PB8_95") (pintype "passive"))
    )
    (net (code "119") (name "Net-(TP6-TP?)") (class "Default")
      (node (ref "TP6") (pin "1") (pinfunction "TP?_1") (pintype "passive"))
      (node (ref "U1") (pin "82") (pinfunction "PD1_82") (pintype "passive"))
    )
    (net (code "120") (name "Net-(TP7-TP?)") (class "Default")
      (node (ref "TP7") (pin "1") (pinfunction "TP?_1") (pintype "passive"))
      (node (ref "U1") (pin "84") (pinfunction "PD3_84") (pintype "passive"))
    )
    (net (code "121") (name "Net-(TP8-TP?)") (class "Default")
      (node (ref "TP8") (pin "1") (pinfunction "TP?_1") (pintype "passive"))
      (node (ref "U1") (pin "86") (pinfunction "PD5_86") (pintype "passive"))
    )
    (net (code "122") (name "Net-(TP9-TP?)") (class "Default")
      (node (ref "TP9") (pin "1") (pinfunction "TP?_1") (pintype "passive"))
      (node (ref "U1") (pin "88") (pinfunction "PD7_88") (pintype "passive"))
    )
    (net (code "123") (name "Net-(TP10-TP?)") (class "Default")
      (node (ref "TP10") (pin "1") (pinfunction "TP?_1") (pintype "passive"))
      (node (ref "U1") (pin "97") (pinfunction "PE0_97") (pintype "passive"))
    )
    (net (code "124") (name "Net-(TP11-TP?)") (class "Default")
      (node (ref "TP11") (pin "1") (pinfunction "TP?_1") (pintype "passive"))
      (node (ref "U1") (pin "80") (pinfunction "PC12_80") (pintype "passive"))
    )
    (net (code "125") (name "Net-(TP12-TP?)") (class "Default")
      (node (ref "TP12") (pin "1") (pinfunction "TP?_1") (pintype "passive"))
      (node (ref "U1") (pin "81") (pinfunction "PD0_81") (pintype "passive"))
    )
    (net (code "126") (name "Net-(TP13-TP?)") (class "Default")
      (node (ref "TP13") (pin "1") (pinfunction "TP?_1") (pintype "passive"))
      (node (ref "U1") (pin "83") (pinfunction "PD2_83") (pintype "passive"))
    )
    (net (code "127") (name "Net-(TP14-TP?)") (class "Default")
      (node (ref "TP14") (pin "1") (pinfunction "TP?_1") (pintype "passive"))
      (node (ref "U1") (pin "85") (pinfunction "PD4_85") (pintype "passive"))
    )
    (net (code "128") (name "Net-(TP15-TP?)") (class "Default")
      (node (ref "TP15") (pin "1") (pinfunction "TP?_1") (pintype "passive"))
      (node (ref "U1") (pin "87") (pinfunction "PD6_87") (pintype "passive"))
    )
    (net (code "129") (name "Net-(TP27-TP?)") (class "Default")
      (node (ref "C27") (pin "2") (pinfunction "2_2") (pintype "passive"))
      (node (ref "R23") (pin "1") (pinfunction "1_1") (pintype "passive"))
      (node (ref "R24") (pin "2") (pinfunction "2_2") (pintype "passive"))
      (node (ref "R26") (pin "1") (pinfunction "1_1") (pintype "passive"))
      (node (ref "TP27") (pin "1") (pinfunction "TP?_1") (pintype "passive"))
    )
    (net (code "130") (name "Net-(TP28-TP?)") (class "Default")
      (node (ref "C32") (pin "2") (pinfunction "2_2") (pintype "passive"))
      (node (ref "R27") (pin "1") (pinfunction "1_1") (pintype "passive"))
      (node (ref "R33") (pin "2") (pinfunction "2_2") (pintype "passive"))
      (node (ref "TP28") (pin "1") (pinfunction "TP?_1") (pintype "passive"))
      (node (ref "U9") (pin "7") (pinfunction "OUT_7") (pintype "passive"))
    )
    (net (code "131") (name "Net-(TP29-TP?)") (class "Default")
      (node (ref "CON2") (pin "1") (pinfunction "1_1") (pintype "passive"))
      (node (ref "R27") (pin "2") (pinfunction "2_2") (pintype "passive"))
      (node (ref "TP29") (pin "1") (pinfunction "TP?_1") (pintype "passive"))
    )
    (net (code "132") (name "Net-(TP45-TP?)") (class "Default")
      (node (ref "TP45") (pin "1") (pinfunction "TP?_1") (pintype "passive"))
      (node (ref "U1") (pin "78") (pinfunction "PC10_78") (pintype "passive"))
    )
    (net (code "133") (name "Net-(TVS1-2)") (class "Default")
      (node (ref "F1") (pin "2") (pinfunction "2_2") (pintype "passive"))
      (node (ref "Q2") (pin "D") (pinfunction "D_D") (pintype "passive"))
      (node (ref "TVS1") (pin "A") (pinfunction "2_A") (pintype "passive"))
    )
    (net (code "134") (name "Net-(U2-VOUT)") (class "Default")
      (node (ref "L1") (pin "2") (pinfunction "2_2") (pintype "passive"))
      (node (ref "U2") (pin "6") (pinfunction "VOUT_6") (pintype "passive"))
    )
    (net (code "135") (name "Net-(U3-D1)") (class "Default")
      (node (ref "R17") (pin "1") (pinfunction "1_1") (pintype "passive"))
      (node (ref "U3") (pin "1") (pinfunction "D1_1") (pintype "passive"))
    )
    (net (code "136") (name "Net-(U3-D2)") (class "Default")
      (node (ref "R13") (pin "2") (pinfunction "2_2") (pintype "passive"))
      (node (ref "U3") (pin "3") (pinfunction "D2_3") (pintype "passive"))
    )
    (net (code "137") (name "Net-(U4-VOUT)") (class "Default")
      (node (ref "L2") (pin "2") (pinfunction "2_2") (pintype "passive"))
      (node (ref "U4") (pin "6") (pinfunction "VOUT_6") (pintype "passive"))
    )
    (net (code "138") (name "Net-(U8-NFB)") (class "Default")
      (node (ref "R25") (pin "2") (pinfunction "2_2") (pintype "passive"))
      (node (ref "R28") (pin "1") (pinfunction "1_1") (pintype "passive"))
      (node (ref "U8") (pin "3") (pinfunction "NFB_3") (pintype "passive"))
    )
    (net (code "139") (name "Net-(U8-Vc)") (class "Default")
      (node (ref "C30") (pin "2") (pinfunction "2_2") (pintype "passive"))
      (node (ref "C31") (pin "2") (pinfunction "2_2") (pintype "passive"))
      (node (ref "U8") (pin "1") (pinfunction "Vc_1") (pintype "passive"))
    )
    (net (code "140") (name "Net-(U8-Vsw)") (class "Default")
      (node (ref "D11") (pin "A") (pinfunction "A_A") (pintype "passive"))
      (node (ref "T1") (pin "3") (pinfunction "3_3") (pintype "passive"))
      (node (ref "U8") (pin "8") (pinfunction "Vsw_8") (pintype "passive"))
    )
    (net (code "141") (name "Net-(U9-COMP)") (class "Default")
      (node (ref "C32") (pin "1") (pinfunction "1_1") (pintype "passive"))
      (node (ref "U9") (pin "5") (pinfunction "COMP_5") (pintype "passive"))
    )
    (net (code "142") (name "Net-(U9-IN+)") (class "Default")
      (node (ref "R24") (pin "1") (pinfunction "1_1") (pintype "passive"))
      (node (ref "U9") (pin "2") (pinfunction "IN+_2") (pintype "passive"))
    )
    (net (code "143") (name "Net-(U9-IN-)") (class "Default")
      (node (ref "R33") (pin "1") (pinfunction "1_1") (pintype "passive"))
      (node (ref "R37") (pin "2") (pinfunction "2_2") (pintype "passive"))
      (node (ref "U9") (pin "1") (pinfunction "IN-_1") (pintype "passive"))
    )
    (net (code "144") (name "Net-(U16-FB)") (class "Default")
      (node (ref "R38") (pin "2") (pinfunction "2_2") (pintype "passive"))
      (node (ref "R39") (pin "1") (pinfunction "1_1") (pintype "passive"))
      (node (ref "U16") (pin "2") (pinfunction "FB_2") (pintype "passive"))
    )
    (net (code "145") (name "Net-(U16-Vc)") (class "Default")
      (node (ref "C42") (pin "2") (pinfunction "2_2") (pintype "passive"))
      (node (ref "C43") (pin "2") (pinfunction "2_2") (pintype "passive"))
      (node (ref "U16") (pin "1") (pinfunction "Vc_1") (pintype "passive"))
    )
    (net (code "146") (name "Net-(U16-Vsw)") (class "Default")
      (node (ref "D12") (pin "A") (pinfunction "A_A") (pintype "passive"))
      (node (ref "L4") (pin "1") (pinfunction "1_1") (pintype "passive"))
      (node (ref "U16") (pin "8") (pinfunction "Vsw_8") (pintype "passive"))
    )
    (net (code "147") (name "Net-(U21-Lx)") (class "Default")
      (node (ref "L5") (pin "1") (pinfunction "1_1") (pintype "passive"))
      (node (ref "U21") (pin "3") (pinfunction "Lx_3") (pintype "passive"))
    )
    (net (code "148") (name "Net-(USB-ID)") (class "Default")
      (node (ref "JO3") (pin "2") (pinfunction "2_2") (pintype "passive"))
      (node (ref "USB") (pin "4") (pinfunction "ID_4") (pintype "power_in"))
    )
    (net (code "149") (name "Net-(USB-SHIELD)") (class "Default")
      (node (ref "L6") (pin "1") (pinfunction "1_1") (pintype "passive"))
      (node (ref "USB") (pin "0") (pinfunction "SHIELD_0") (pintype "power_in"))
    )
    (net (code "150") (name "VINPWR") (class "Default")
      (node (ref "C22") (pin "1") (pinfunction "1_1") (pintype "passive"))
      (node (ref "C37") (pin "1") (pinfunction "1_1") (pintype "passive"))
      (node (ref "C51") (pin "1") (pinfunction "1_1") (pintype "passive"))
      (node (ref "D9") (pin "A") (pinfunction "A_A") (pintype "passive"))
      (node (ref "L4") (pin "2") (pinfunction "2_2") (pintype "passive"))
      (node (ref "Q2") (pin "S") (pinfunction "S_S") (pintype "passive"))
      (node (ref "T1") (pin "1") (pinfunction "P1_1") (pintype "passive"))
      (node (ref "TP42") (pin "1") (pinfunction "TP?_1") (pintype "passive"))
      (node (ref "U16") (pin "5") (pinfunction "Vin_5") (pintype "passive"))
      (node (ref "U21") (pin "1") (pinfunction "~{SHDN}_1") (pintype "passive"))
      (node (ref "U21") (pin "4") (pinfunction "VIN_4") (pintype "passive"))
      (node (ref "U8") (pin "5") (pinfunction "Vin_5") (pintype "passive"))
    )
    (net (code "151") (name "VUSB") (class "Default")
      (node (ref "D8") (pin "1") (pinfunction "A_1") (pintype "passive"))
      (node (ref "JO2") (pin "2") (pinfunction "2_2") (pintype "passive"))
      (node (ref "USB") (pin "1") (pinfunction "VCC_1") (pintype "power_in"))
    )
    (net (code "152") (name "unconnected-(CON3-Pad32)") (class "Default")
      (node (ref "CON3") (pin "32") (pinfunction "32_32") (pintype "passive+no_connect"))
    )
    (net (code "153") (name "unconnected-(S1-Pad3)") (class "Default")
      (node (ref "S1") (pin "3") (pinfunction "3_3") (pintype "passive+no_connect"))
    )
    (net (code "154") (name "unconnected-(U8-FB-Pad2)") (class "Default")
      (node (ref "U8") (pin "2") (pinfunction "FB_2") (pintype "passive"))
    )
    (net (code "155") (name "unconnected-(U16-NFB-Pad3)") (class "Default")
      (node (ref "U16") (pin "3") (pinfunction "NFB_3") (pintype "passive"))
    )
  )
)
